# TinyShuffle_v_0b.net
KiCad netlist of a schematic drawn in Altium Designer
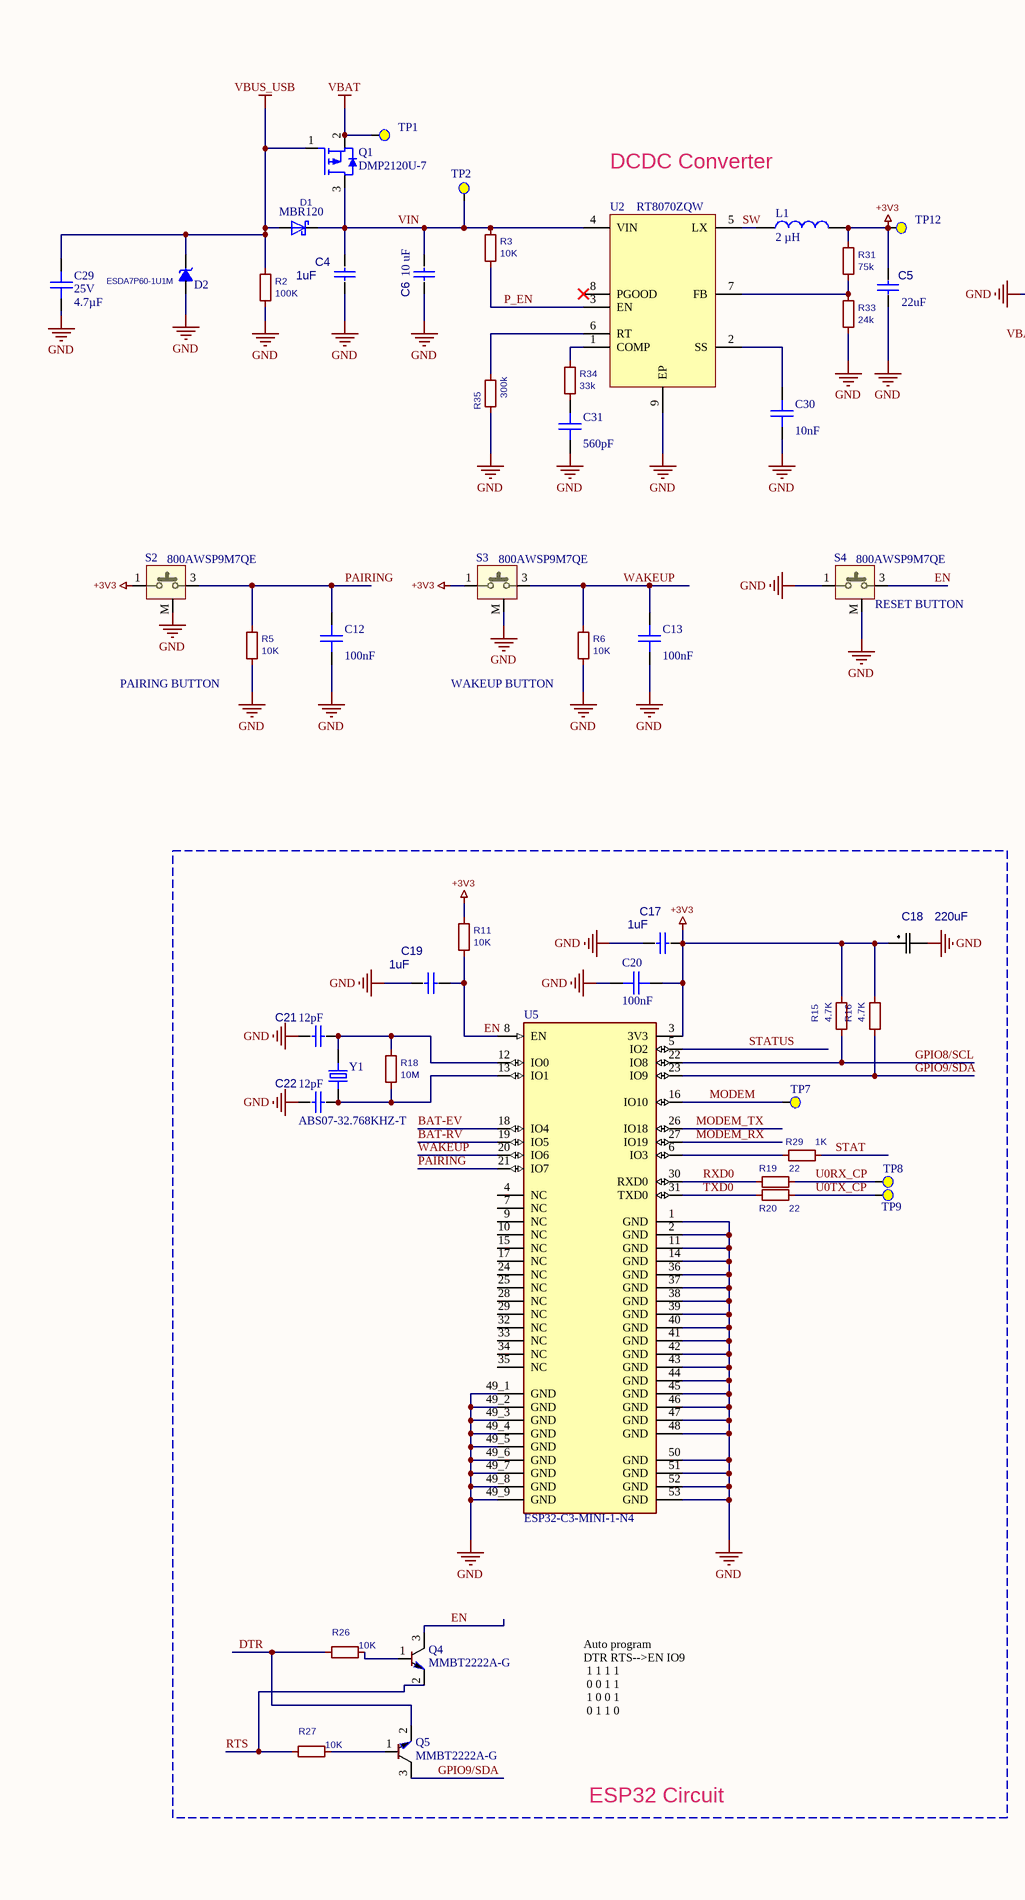
[diagram p0: TinyShuffle v.0b.SchDoc, left]
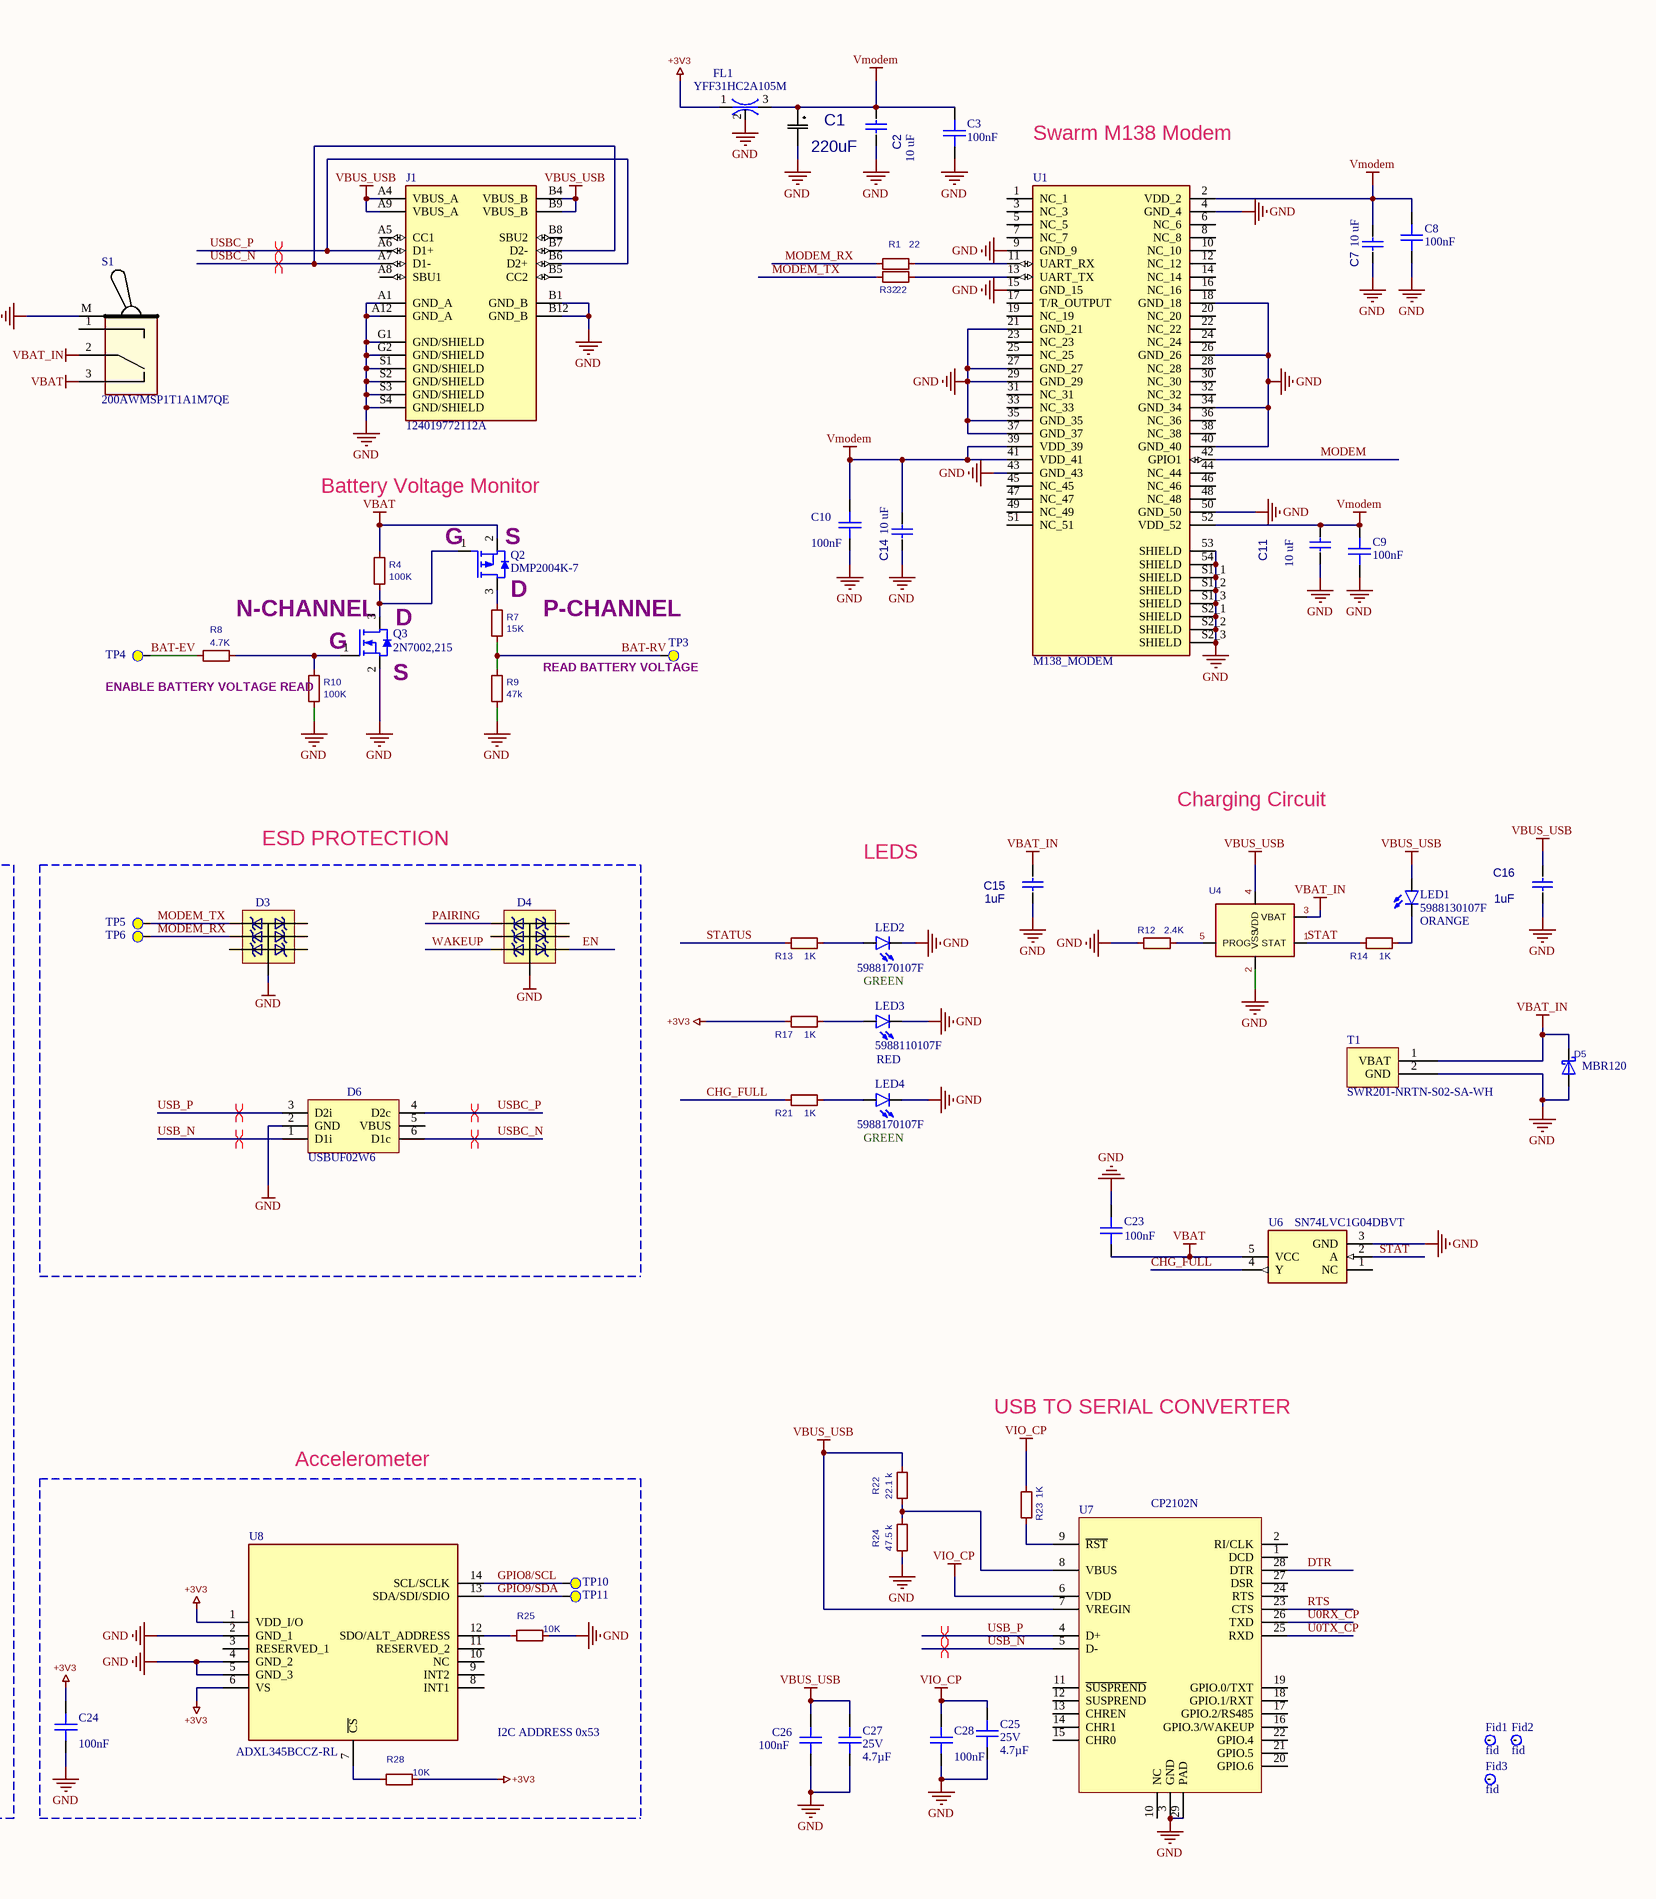
[diagram p1: TinyShuffle v.0b.SchDoc, right]

(export (version "E")
  (design (tool "Eeschema 10.0.6"))
  (components
    (comp (ref "C1")
      (value "220uF")
      (footprint "CHEMI-H70")
      (description "CAP ALUM POLY 220UF 20% 6.3V SMD")
      (fields
        (field (name "MANUFACTURER") "Nippon Chemi-Con")
        (field (name "MANUFACTURERPARTNUMBER") "APXA6R3ARA221MH70G")
        (field (name "COPYRIGHT") "Copyright (C) 2022 Ultra Librarian. All rights reserved.")
      )
      (libsource (lib "TinyShuffle v.0") (part "APXA6R3ARA221MH7"))
    )
    (comp (ref "C2")
      (value "10 uF")
      (footprint "0603 Capacitor")
      (description "25V 10UF X5R ±20% 0603 MLCC")
      (fields
        (field (name "MANUFACTURER") "Samsung Electro-Mechanics")
        (field (name "MANUFACTURERPARTNUMBER") "CL10A106MA8NRNC")
      )
      (libsource (lib "*") (part "CAPC1608N-0.1UF"))
    )
    (comp (ref "C3")
      (value "CL10B104KB8NNWC")
      (footprint "CAPC160X80X90L35L")
      (description "CAP CER 0.1UF 50V X7R 0603")
      (fields
        (field (name "CAPACITANCE") "100nF")
        (field (name "TOLERANCE") "10%")
        (field (name "MANUFACTURER") "Samsung Electro-Mechanics")
      )
      (libsource (lib "VDroid Server") (part "CAP general symbol S00567"))
    )
    (comp (ref "C4")
      (value "1uF")
      (footprint "0603 Capacitor")
      (description "CAP CER 1UF 25V X7R 0603")
      (fields
        (field (name "MANUFACTURER") "YAGEO")
        (field (name "MANUFACTURERPARTNUMBER") "CC0603KRX7R8BB105")
      )
      (libsource (lib "*") (part "CAPC1608N-0.1UF"))
    )
    (comp (ref "C5")
      (value "22uF")
      (footprint "CAPC2012X135N")
      (description "CAP CER 22UF 16V X5R 0805")
      (fields
        (field (name "MANUFACTURER") "Samsung Electro-Mechanics")
        (field (name "MANUFACTURERPARTNUMBER") "CL21A226MOQNNNE")
      )
      (libsource (lib "TinyShuffle v.0") (part "CL21A226MOQNNNE"))
    )
    (comp (ref "C6")
      (value "10 uF")
      (footprint "0603 Capacitor")
      (description "25V 10UF X5R ±20% 0603 MLCC")
      (fields
        (field (name "MANUFACTURER") "Samsung Electro-Mechanics")
        (field (name "MANUFACTURERPARTNUMBER") "CL10A106MA8NRNC")
      )
      (libsource (lib "*") (part "CAPC1608N-0.1UF"))
    )
    (comp (ref "C7")
      (value "10 uF")
      (footprint "0603 Capacitor")
      (description "25V 10UF X5R ±20% 0603 MLCC")
      (fields
        (field (name "MANUFACTURER") "Samsung Electro-Mechanics")
        (field (name "MANUFACTURERPARTNUMBER") "CL10A106MA8NRNC")
      )
      (libsource (lib "*") (part "CAPC1608N-0.1UF"))
    )
    (comp (ref "C8")
      (value "CL10B104KB8NNWC")
      (footprint "CAPC160X80X90L35L")
      (description "CAP CER 0.1UF 50V X7R 0603")
      (fields
        (field (name "CAPACITANCE") "100nF")
        (field (name "TOLERANCE") "10%")
        (field (name "MANUFACTURER") "Samsung Electro-Mechanics")
      )
      (libsource (lib "VDroid Server") (part "CAP general symbol S00567"))
    )
    (comp (ref "C9")
      (value "CL10B104KB8NNWC")
      (footprint "CAPC160X80X90L35L")
      (description "CAP CER 0.1UF 50V X7R 0603")
      (fields
        (field (name "CAPACITANCE") "100nF")
        (field (name "TOLERANCE") "10%")
        (field (name "MANUFACTURER") "Samsung Electro-Mechanics")
      )
      (libsource (lib "VDroid Server") (part "CAP general symbol S00567"))
    )
    (comp (ref "C10")
      (value "CL10B104KB8NNWC")
      (footprint "CAPC160X80X90L35L")
      (description "CAP CER 0.1UF 50V X7R 0603")
      (fields
        (field (name "CAPACITANCE") "100nF")
        (field (name "TOLERANCE") "10%")
        (field (name "MANUFACTURER") "Samsung Electro-Mechanics")
      )
      (libsource (lib "VDroid Server") (part "CAP general symbol S00567"))
    )
    (comp (ref "C11")
      (value "10 uF")
      (footprint "0603 Capacitor")
      (description "25V 10UF X5R ±20% 0603 MLCC")
      (fields
        (field (name "MANUFACTURER") "Samsung Electro-Mechanics")
        (field (name "MANUFACTURERPARTNUMBER") "CL10A106MA8NRNC")
      )
      (libsource (lib "*") (part "CAPC1608N-0.1UF"))
    )
    (comp (ref "C12")
      (value "CL10B104KB8NNWC")
      (footprint "CAPC160X80X90L35L")
      (description "CAP CER 0.1UF 50V X7R 0603")
      (fields
        (field (name "CAPACITANCE") "100nF")
        (field (name "TOLERANCE") "10%")
        (field (name "MANUFACTURER") "Samsung Electro-Mechanics")
      )
      (libsource (lib "VDroid Server") (part "CAP general symbol S00567"))
    )
    (comp (ref "C13")
      (value "CL10B104KB8NNWC")
      (footprint "CAPC160X80X90L35L")
      (description "CAP CER 0.1UF 50V X7R 0603")
      (fields
        (field (name "CAPACITANCE") "100nF")
        (field (name "TOLERANCE") "10%")
        (field (name "MANUFACTURER") "Samsung Electro-Mechanics")
      )
      (libsource (lib "VDroid Server") (part "CAP general symbol S00567"))
    )
    (comp (ref "C14")
      (value "10 uF")
      (footprint "0603 Capacitor")
      (description "25V 10UF X5R ±20% 0603 MLCC")
      (fields
        (field (name "MANUFACTURER") "Samsung Electro-Mechanics")
        (field (name "MANUFACTURERPARTNUMBER") "CL10A106MA8NRNC")
      )
      (libsource (lib "*") (part "CAPC1608N-0.1UF"))
    )
    (comp (ref "C15")
      (value "1uF")
      (footprint "0603 Capacitor")
      (description "CAP CER 1UF 25V X7R 0603")
      (fields
        (field (name "MANUFACTURER") "YAGEO")
        (field (name "MANUFACTURERPARTNUMBER") "CC0603KRX7R8BB105")
      )
      (libsource (lib "*") (part "CAPC1608N-0.1UF"))
    )
    (comp (ref "C16")
      (value "1uF")
      (footprint "0603 Capacitor")
      (description "CAP CER 1UF 25V X7R 0603")
      (fields
        (field (name "MANUFACTURER") "YAGEO")
        (field (name "MANUFACTURERPARTNUMBER") "CC0603KRX7R8BB105")
      )
      (libsource (lib "*") (part "CAPC1608N-0.1UF"))
    )
    (comp (ref "C17")
      (value "1uF")
      (footprint "0603 Capacitor")
      (description "CAP CER 1UF 25V X7R 0603")
      (fields
        (field (name "MANUFACTURER") "YAGEO")
        (field (name "MANUFACTURERPARTNUMBER") "CC0603KRX7R8BB105")
      )
      (libsource (lib "*") (part "CAPC1608N-0.1UF"))
    )
    (comp (ref "C18")
      (value "220uF")
      (footprint "CHEMI-H70")
      (description "CAP ALUM POLY 220UF 20% 6.3V SMD")
      (fields
        (field (name "MANUFACTURER") "Nippon Chemi-Con")
        (field (name "MANUFACTURERPARTNUMBER") "APXA6R3ARA221MH70G")
        (field (name "COPYRIGHT") "Copyright (C) 2022 Ultra Librarian. All rights reserved.")
      )
      (libsource (lib "TinyShuffle v.0") (part "APXA6R3ARA221MH7"))
    )
    (comp (ref "C19")
      (value "1uF")
      (footprint "0603 Capacitor")
      (description "CAP CER 1UF 25V X7R 0603")
      (fields
        (field (name "MANUFACTURER") "YAGEO")
        (field (name "MANUFACTURERPARTNUMBER") "CC0603KRX7R8BB105")
      )
      (libsource (lib "*") (part "CAPC1608N-0.1UF"))
    )
    (comp (ref "C20")
      (value "CL10B104KB8NNWC")
      (footprint "CAPC160X80X90L35L")
      (description "CAP CER 0.1UF 50V X7R 0603")
      (fields
        (field (name "CAPACITANCE") "100nF")
        (field (name "TOLERANCE") "10%")
        (field (name "MANUFACTURER") "Samsung Electro-Mechanics")
      )
      (libsource (lib "VDroid Server") (part "CAP general symbol S00567"))
    )
    (comp (ref "C21")
      (value "12pF")
      (footprint "0603 Capacitor")
      (description "CAP CER 12PF NP0 0603")
      (fields
        (field (name "MANUFACTURER") "Murata Electronics")
        (field (name "MANUFACTURERPARTNUMBER") "GRM1885C2A120JA01D")
      )
      (libsource (lib "*") (part "CAPC1608N-0.1UF"))
    )
    (comp (ref "C22")
      (value "12pF")
      (footprint "0603 Capacitor")
      (description "CAP CER 12PF NP0 0603")
      (fields
        (field (name "MANUFACTURER") "Murata Electronics")
        (field (name "MANUFACTURERPARTNUMBER") "GRM1885C2A120JA01D")
      )
      (libsource (lib "*") (part "CAPC1608N-0.1UF"))
    )
    (comp (ref "C23")
      (value "CL10B104KB8NNWC")
      (footprint "CAPC160X80X90L35L")
      (description "CAP CER 0.1UF 50V X7R 0603")
      (fields
        (field (name "CAPACITANCE") "100nF")
        (field (name "TOLERANCE") "10%")
        (field (name "MANUFACTURER") "Samsung Electro-Mechanics")
      )
      (libsource (lib "VDroid Server") (part "CAP general symbol S00567"))
    )
    (comp (ref "C24")
      (value "CL10B104KB8NNWC")
      (footprint "CAPC160X80X90L35L")
      (description "CAP CER 0.1UF 50V X7R 0603")
      (fields
        (field (name "CAPACITANCE") "100nF")
        (field (name "TOLERANCE") "10%")
        (field (name "MANUFACTURER") "Samsung Electro-Mechanics")
      )
      (libsource (lib "VDroid Server") (part "CAP general symbol S00567"))
    )
    (comp (ref "C25")
      (value "GRM188R61E475KE11D")
      (footprint "CAPC160X80X90L35L")
      (description "CAP CER 4.7UF 25V X5R 0603")
      (fields
        (field (name "VOLTAGE RATING") "25V")
        (field (name "TOLERANCE") "10%")
        (field (name "CAPACITANCE") "4.7µF")
        (field (name "MANUFACTURER") "Murata Electronics")
      )
      (libsource (lib "VDroid Server") (part "CAP general symbol S00567"))
    )
    (comp (ref "C26")
      (value "CL10B104KB8NNWC")
      (footprint "CAPC160X80X90L35L")
      (description "CAP CER 0.1UF 50V X7R 0603")
      (fields
        (field (name "CAPACITANCE") "100nF")
        (field (name "TOLERANCE") "10%")
        (field (name "MANUFACTURER") "Samsung Electro-Mechanics")
      )
      (libsource (lib "VDroid Server") (part "CAP general symbol S00567"))
    )
    (comp (ref "C27")
      (value "GRM188R61E475KE11D")
      (footprint "CAPC160X80X90L35L")
      (description "CAP CER 4.7UF 25V X5R 0603")
      (fields
        (field (name "VOLTAGE RATING") "25V")
        (field (name "TOLERANCE") "10%")
        (field (name "CAPACITANCE") "4.7µF")
        (field (name "MANUFACTURER") "Murata Electronics")
      )
      (libsource (lib "VDroid Server") (part "CAP general symbol S00567"))
    )
    (comp (ref "C28")
      (value "CL10B104KB8NNWC")
      (footprint "CAPC160X80X90L35L")
      (description "CAP CER 0.1UF 50V X7R 0603")
      (fields
        (field (name "CAPACITANCE") "100nF")
        (field (name "TOLERANCE") "10%")
        (field (name "MANUFACTURER") "Samsung Electro-Mechanics")
      )
      (libsource (lib "VDroid Server") (part "CAP general symbol S00567"))
    )
    (comp (ref "C29")
      (value "GRM188R61E475KE11D")
      (footprint "CAPC160X80X90L35L")
      (description "CAP CER 4.7UF 25V X5R 0603")
      (fields
        (field (name "VOLTAGE RATING") "25V")
        (field (name "TOLERANCE") "10%")
        (field (name "CAPACITANCE") "4.7µF")
        (field (name "MANUFACTURER") "Murata Electronics")
      )
      (libsource (lib "VDroid Server") (part "CAP general symbol S00567"))
    )
    (comp (ref "C30")
      (value "CL10B103KB8NNNC")
      (footprint "CAPC160X80X90L35L")
      (description "CAP CER 10000PF 50V X7R 0603")
      (fields
        (field (name "CAPACITANCE") "10nF")
        (field (name "TOLERANCE") "10%")
        (field (name "MANUFACTURER") "Samsung Electro-Mechanics")
      )
      (libsource (lib "VDroid Server") (part "CAP general symbol S00567"))
    )
    (comp (ref "C31")
      (value "CL10C561JB8NFNC")
      (footprint "CAPC160X80X90L35L")
      (description "CAP CER 560PF 50V C0G/NP0 0603")
      (fields
        (field (name "CAPACITANCE") "560pF")
        (field (name "TOLERANCE") "10%")
        (field (name "MANUFACTURER") "Samsung Electro-Mechanics")
      )
      (libsource (lib "VDroid Server") (part "CAP general symbol S00567"))
    )
    (comp (ref "D1")
      (value "MBR120")
      (footprint "SODFL3616X98N")
      (description "20V 600mV@1A 1A SOD-123 Schottky Barrier Diodes (SBD) ROHS")
      (fields (field (name "MANUFACTURERPARTNUMBER") "LMBR120FT1G") (field (name "GENERIC PART") "no"))
      (libsource (lib "TinyShuffle v.0b") (part "MBR0520"))
    )
    (comp (ref "D2")
      (value "ESDA7P60-1U1M")
      (footprint "ST_1610")
      (description "TVS DIODE 5V 11.6V 1610")
      (fields (field (name "MANUFACTURER") "STMicroelectronics"))
      (libsource (lib "Diodes") (part "ESDA7P60-1U1M"))
    )
    (comp (ref "D3")
      (value "UCLAMP3306P.TCT")
      (footprint "SLP1616P6")
      (description "TVS DIODE 3.3V 8V SLP1616P6")
      (fields (field (name "MANUFACTURER") "Semtech"))
      (libsource (lib "Diodes") (part "UCLAMP3306P.TCT"))
    )
    (comp (ref "D4")
      (value "UCLAMP3306P.TCT")
      (footprint "SLP1616P6")
      (description "TVS DIODE 3.3V 8V SLP1616P6")
      (fields (field (name "MANUFACTURER") "Semtech"))
      (libsource (lib "Diodes") (part "UCLAMP3306P.TCT"))
    )
    (comp (ref "D5")
      (value "MBR120")
      (footprint "SODFL3616X98N")
      (description "20V 600mV@1A 1A SOD-123 Schottky Barrier Diodes (SBD) ROHS")
      (fields (field (name "MANUFACTURERPARTNUMBER") "LMBR120FT1G") (field (name "GENERIC PART") "no"))
      (libsource (lib "TinyShuffle v.0b") (part "MBR0520"))
    )
    (comp (ref "D6")
      (value "USBUF02W6")
      (footprint "SOT323-6L")
      (description "FILTER RC(PI) 22 OHM/47PF SMD")
      (fields (field (name "MANUFACTURER") "STMicroelectronics"))
      (libsource (lib "Diodes") (part "NUF2221W1T2G"))
    )
    (comp (ref "Fid1") (value "fid") (footprint "Fiducial mark 1") (libsource (lib "SensiEdge") (part "fid")))
    (comp (ref "Fid2") (value "fid") (footprint "Fiducial mark 1") (libsource (lib "SensiEdge") (part "fid")))
    (comp (ref "Fid3") (value "fid") (footprint "Fiducial mark 1") (libsource (lib "SensiEdge") (part "fid")))
    (comp (ref "FL1")
      (value "YFF31HC2A105M")
      (footprint "FIL_YFF31HC2A105M")
      (description "1ÂµF Feed Through Capacitor 100V 6A 5mOhm 1206 (3216 Metric), 4 PC Pad")
      (fields (field (name "MANUFACTURER") "TDK") (field (name "DIGI-KEY_PART_NUMBER") "445-16151-1-ND"))
      (libsource (lib "TinyShuffle v.0") (part "YFF31HC2A105M"))
    )
    (comp (ref "J1")
      (value "124019772112A")
      (footprint "TinyShuffle v.0:AMPHENOL_124019772112A")
      (description "USB2.0, TOP MOUNT, R/A, 16 PIN, DUAL")
      (fields (field (name "MANUFACTURER") "Amphenol Commercial Products"))
      (libsource (lib "TinyShuffle v.0") (part "124019772112A"))
    )
    (comp (ref "L1")
      (value "2 µH")
      (footprint "INDC8080X42L")
      (description "FIXED IND 2UH 6.3A 11.7 MOHM SMD")
      (fields
        (field (name "MANUFACTURERPARTNUMBER") "NR8040T2R0N")
        (field (name "MANUFACTURER") "Taiyo Yuden")
      )
      (libsource (lib "TinyShuffle v.0") (part "NR8040T2R0N"))
    )
    (comp (ref "LED1")
      (value "5988130107F")
      (footprint "TinyShuffle v.0:LEDC2012X70N")
      (description "Orange 605nm LED Indication - Discrete 2V 0805 (2012 Metric)")
      (fields
        (field (name "MANUFACTURERPARTNUMBER") "598-8110-107F")
        (field (name "MANUFACTURER") "Dialight")
        (field (name "ALTIUM_VALUE") "ORANGE")
      )
      (libsource (lib "TinyShuffle v.0") (part "598_SERIES_LED"))
    )
    (comp (ref "LED2")
      (value "5988170107F")
      (footprint "LEDC2012X70N")
      (description "Green 566nm LED Indication - Discrete 2V 0805 (2012 Metric)")
      (fields
        (field (name "MANUFACTURERPARTNUMBER") "598-8110-107F")
        (field (name "MANUFACTURER") "Dialight")
        (field (name "ALTIUM_VALUE") "GREEN")
      )
      (libsource (lib "TinyShuffle v.0") (part "598_SERIES_LED"))
    )
    (comp (ref "LED3")
      (value "5988110107F")
      (footprint "TinyShuffle v.0:LEDC2012X70N")
      (description "Red 635nm LED Indication - Discrete 2.2V 0805 _2012 Metric_")
      (fields
        (field (name "MANUFACTURERPARTNUMBER") "598-8110-107F")
        (field (name "MANUFACTURER") "Dialight")
        (field (name "ALTIUM_VALUE") "RED")
      )
      (libsource (lib "TinyShuffle v.0") (part "598_SERIES_LED"))
    )
    (comp (ref "LED4")
      (value "5988170107F")
      (footprint "TinyShuffle v.0:LEDC2012X70N")
      (description "Green 566nm LED Indication - Discrete 2V 0805 (2012 Metric)")
      (fields
        (field (name "MANUFACTURERPARTNUMBER") "598-8110-107F")
        (field (name "MANUFACTURER") "Dialight")
        (field (name "ALTIUM_VALUE") "GREEN")
      )
      (libsource (lib "TinyShuffle v.0") (part "598_SERIES_LED"))
    )
    (comp (ref "Q1")
      (value "DMP2120U-7")
      (footprint "SOT23-3P95_237X112L50X40L")
      (description "MOSFET P-CH 20V 3.8A SOT23")
      (fields (field (name "MANUFACTURER") "Diodes Incorporated"))
      (libsource (lib "VDroid Server") (part "P-type channel MOSFET S00673 (1-G 2-S 3-D)"))
    )
    (comp (ref "Q2")
      (value "DMP2004K-7")
      (footprint "SOT23-3P95_237X112L50X40L")
      (description "MOSFET P-CH 20V 600MA SOT23-3")
      (fields (field (name "MANUFACTURER") "Diodes Incorporated"))
      (libsource (lib "VDroid Server") (part "P-type channel MOSFET S00673 (1-G 2-S 3-D)"))
    )
    (comp (ref "Q3")
      (value "2N7002,215")
      (footprint "SOT23-3P95_237X112L50X40L")
      (description "Power MOSFET, N Channel, 60 V, 300 mA, 2.8 ohm, SOT-23, Surface Mount")
      (fields (field (name "MANUFACTURER") "Nexperia USA Inc."))
      (libsource (lib "VDroid Server") (part "N-type channel MOSFET S00674 (1-G 2-S 3-D)"))
    )
    (comp (ref "Q4")
      (value "MMBT2222A-G")
      (footprint "SOT96P237X111-3N")
      (description "Integrated Circuit")
      (fields
        (field (name "MANUFACTURER") "Comchip Technology")
        (field (name "MOUSER PART NUMBER") "863-MMBT2222ALT1G")
      )
      (libsource (lib "TinyShuffle v.0") (part "MMBT2222ALT1G"))
    )
    (comp (ref "Q5")
      (value "MMBT2222A-G")
      (footprint "SOT96P237X111-3N")
      (description "Integrated Circuit")
      (fields
        (field (name "MANUFACTURER") "Comchip Technology")
        (field (name "MOUSER PART NUMBER") "863-MMBT2222ALT1G")
      )
      (libsource (lib "") (part "MMBT2222ALT1G_1"))
    )
    (comp (ref "R1")
      (value "22")
      (footprint "RES0603")
      (description "RES 22OHM 1/10W 1% 0603 SMD")
      (fields (field (name "MANUFACTURERPARTNUMBER") "RC0603FR-0722RL") (field (name "GENERIC PART") "no"))
      (libsource (lib "Vishay_Res_SMD") (part "1K_0603"))
    )
    (comp (ref "R2")
      (value "100K")
      (footprint "RES0603")
      (description "Res General Purpose Thick Film 0603 100k Ohm 1% 1/10W ±100ppm/°C Molded")
      (fields (field (name "MANUFACTURERPARTNUMBER") "CRCW0603100KFKEAHP") (field (name "GENERIC PART") "no"))
      (libsource (lib "Vishay_Res_SMD") (part "100K_0603"))
    )
    (comp (ref "R3")
      (value "10K")
      (footprint "RES0603")
      (description "RES 10.0K OHM 1/10W 1% 0603 SMD Ro HS")
      (fields (field (name "MANUFACTURERPARTNUMBER") "RGA1608P-103-B-T1") (field (name "GENERIC PART") "no"))
      (libsource (lib "Vishay_Res_SMD") (part "100K_0603"))
    )
    (comp (ref "R4")
      (value "100K")
      (footprint "RES0603")
      (description "Res General Purpose Thick Film 0603 100k Ohm 1% 1/10W ±100ppm/°C Molded")
      (fields (field (name "MANUFACTURERPARTNUMBER") "CRCW0603100KFKEAHP") (field (name "GENERIC PART") "no"))
      (libsource (lib "Vishay_Res_SMD") (part "100K_0603"))
    )
    (comp (ref "R5")
      (value "10K")
      (footprint "RES0603")
      (description "RES 10.0K OHM 1/10W 1% 0603 SMD Ro HS")
      (fields (field (name "MANUFACTURERPARTNUMBER") "RGA1608P-103-B-T1") (field (name "GENERIC PART") "no"))
      (libsource (lib "Vishay_Res_SMD") (part "100K_0603"))
    )
    (comp (ref "R6")
      (value "10K")
      (footprint "RES0603")
      (description "RES 10.0K OHM 1/10W 1% 0603 SMD Ro HS")
      (fields (field (name "MANUFACTURERPARTNUMBER") "RGA1608P-103-B-T1") (field (name "GENERIC PART") "no"))
      (libsource (lib "Vishay_Res_SMD") (part "100K_0603"))
    )
    (comp (ref "R7")
      (value "15K")
      (footprint "RES0603")
      (description "RES 15K OHM 1% 1/10W 0603")
      (fields (field (name "MANUFACTURERPARTNUMBER") "CRCW060315K0FKEAC") (field (name "GENERIC PART") "no"))
      (libsource (lib "Vishay_Res_SMD") (part "330K_0603"))
    )
    (comp (ref "R8")
      (value "4.7K")
      (footprint "RES0603")
      (description "Thin Film Resistors - SMD 1/10W 4.7K ohm 1% 50ppm")
      (fields (field (name "MANUFACTURERPARTNUMBER") "RT0603FRE074K7L") (field (name "MANUFACTURER") "YAGEO"))
      (libsource (lib "") (part "100K_0603_2"))
    )
    (comp (ref "R9")
      (value "47k")
      (footprint "RES0603")
      (description "RES SMD 47K OHM 1% 1/10W 0603")
      (fields (field (name "MANUFACTURERPARTNUMBER") "CRCW060347K0FKTA") (field (name "GENERIC PART") "no"))
      (libsource (lib "Vishay_Res_SMD") (part "100K_0603"))
    )
    (comp (ref "R10")
      (value "100K")
      (footprint "RES0603")
      (description "Res General Purpose Thick Film 0603 100k Ohm 1% 1/10W ±100ppm/°C Molded")
      (fields (field (name "MANUFACTURERPARTNUMBER") "CRCW0603100KFKEAHP") (field (name "GENERIC PART") "no"))
      (libsource (lib "Vishay_Res_SMD") (part "100K_0603"))
    )
    (comp (ref "R11")
      (value "10K")
      (footprint "RES0603")
      (description "RES 10.0K OHM 1/10W 1% 0603 SMD Ro HS")
      (fields (field (name "MANUFACTURERPARTNUMBER") "RGA1608P-103-B-T1") (field (name "GENERIC PART") "no"))
      (libsource (lib "Vishay_Res_SMD") (part "100K_0603"))
    )
    (comp (ref "R12")
      (value "2.4K")
      (footprint "RES0603")
      (description "2.4 kOhms ±1% 0.1W, 1/10W Chip Resistor 0603 (1608 Metric) Thick Film")
      (fields (field (name "MANUFACTURERPARTNUMBER") "CRCW06032K40FKEAC") (field (name "GENERIC PART") "no"))
      (libsource (lib "Vishay_Res_SMD") (part "10K_0603"))
    )
    (comp (ref "R13")
      (value "1K")
      (footprint "RES0603")
      (description "RES 1.00K OHM 1/10W 1% 0603 SMD")
      (fields (field (name "MANUFACTURERPARTNUMBER") "CRCW06031K00FKEAHP") (field (name "GENERIC PART") "no"))
      (libsource (lib "Vishay_Res_SMD") (part "1K_0603"))
    )
    (comp (ref "R14")
      (value "1K")
      (footprint "RES0603")
      (description "RES 1.00K OHM 1/10W 1% 0603 SMD")
      (fields (field (name "MANUFACTURERPARTNUMBER") "CRCW06031K00FKEAHP") (field (name "GENERIC PART") "no"))
      (libsource (lib "Vishay_Res_SMD") (part "1K_0603"))
    )
    (comp (ref "R15")
      (value "4.7K")
      (footprint "RES0603")
      (description "Thin Film Resistors - SMD 1/10W 4.7K ohm 1% 50ppm")
      (fields (field (name "MANUFACTURERPARTNUMBER") "RT0603FRE074K7L") (field (name "MANUFACTURER") "YAGEO"))
      (libsource (lib "") (part "100K_0603_1"))
    )
    (comp (ref "R16")
      (value "4.7K")
      (footprint "RES0603")
      (description "Thin Film Resistors - SMD 1/10W 4.7K ohm 1% 50ppm")
      (fields (field (name "MANUFACTURERPARTNUMBER") "RT0603FRE074K7L") (field (name "MANUFACTURER") "YAGEO"))
      (libsource (lib "") (part "100K_0603_1"))
    )
    (comp (ref "R17")
      (value "1K")
      (footprint "RES0603")
      (description "RES 1.00K OHM 1/10W 1% 0603 SMD")
      (fields (field (name "MANUFACTURERPARTNUMBER") "CRCW06031K00FKEAHP") (field (name "GENERIC PART") "no"))
      (libsource (lib "Vishay_Res_SMD") (part "1K_0603"))
    )
    (comp (ref "R18")
      (value "10M")
      (footprint "RES0603")
      (description "Res Thick Film 0603 10M Ohm 1% 1/10W ±200ppm/°C Molded SMD SMD Paper T/R")
      (fields (field (name "GENERIC PART") "YES") (field (name "MANUFACTURERPARTNUMBER") "CRCW060310M0JNEA"))
      (libsource (lib "Vishay_Res_SMD") (part "100K_0603"))
    )
    (comp (ref "R19")
      (value "22")
      (footprint "RES0603")
      (description "RES 22OHM 1/10W 1% 0603 SMD")
      (fields (field (name "MANUFACTURERPARTNUMBER") "RC0603FR-0722RL") (field (name "GENERIC PART") "no"))
      (libsource (lib "Vishay_Res_SMD") (part "1K_0603"))
    )
    (comp (ref "R20")
      (value "22")
      (footprint "RES0603")
      (description "RES 22OHM 1/10W 1% 0603 SMD")
      (fields (field (name "MANUFACTURERPARTNUMBER") "RC0603FR-0722RL") (field (name "GENERIC PART") "no"))
      (libsource (lib "Vishay_Res_SMD") (part "1K_0603"))
    )
    (comp (ref "R21")
      (value "1K")
      (footprint "RES0603")
      (description "RES 1.00K OHM 1/10W 1% 0603 SMD")
      (fields (field (name "MANUFACTURERPARTNUMBER") "CRCW06031K00FKEAHP") (field (name "GENERIC PART") "no"))
      (libsource (lib "Vishay_Res_SMD") (part "1K_0603"))
    )
    (comp (ref "R22")
      (value "22.1 k")
      (footprint "RES0603")
      (description "RES SMD 22.1K OHM 1% 1/10W 0603")
      (fields
        (field (name "MANUFACTURERPARTNUMBER") "CRCW060322K1FKEA")
        (field (name "MANUFACTURER") "Vishay")
      )
      (libsource (lib "") (part "1K_0603_1"))
    )
    (comp (ref "R23")
      (value "1K")
      (footprint "RES0603")
      (description "RES 1.00K OHM 1/10W 1% 0603 SMD")
      (fields (field (name "MANUFACTURERPARTNUMBER") "CRCW06031K00FKEAHP") (field (name "GENERIC PART") "no"))
      (libsource (lib "") (part "1K_0603_1"))
    )
    (comp (ref "R24")
      (value "47.5 k")
      (footprint "RES0603")
      (description "RES 47.5K OHM 1% 1/10W 0603")
      (fields
        (field (name "MANUFACTURERPARTNUMBER") "CRCW060347K5FKEAC")
        (field (name "MANUFACTURER") "Vishay")
      )
      (libsource (lib "") (part "1K_0603_1"))
    )
    (comp (ref "R25")
      (value "10K")
      (footprint "RES0603")
      (description "RES 10.0K OHM 1/10W 1% 0603 SMD Ro HS")
      (fields (field (name "MANUFACTURERPARTNUMBER") "RGA1608P-103-B-T1") (field (name "GENERIC PART") "no"))
      (libsource (lib "") (part "100K_0603_2"))
    )
    (comp (ref "R26")
      (value "10K")
      (footprint "RES0603")
      (description "RES 10.0K OHM 1/10W 1% 0603 SMD Ro HS")
      (fields (field (name "MANUFACTURERPARTNUMBER") "RGA1608P-103-B-T1") (field (name "GENERIC PART") "no"))
      (libsource (lib "") (part "100K_0603_2"))
    )
    (comp (ref "R27")
      (value "10K")
      (footprint "RES0603")
      (description "RES 10.0K OHM 1/10W 1% 0603 SMD Ro HS")
      (fields (field (name "MANUFACTURERPARTNUMBER") "RGA1608P-103-B-T1") (field (name "GENERIC PART") "no"))
      (libsource (lib "") (part "100K_0603_2"))
    )
    (comp (ref "R28")
      (value "10K")
      (footprint "RES0603")
      (description "RES 10.0K OHM 1/10W 1% 0603 SMD Ro HS")
      (fields (field (name "MANUFACTURERPARTNUMBER") "RGA1608P-103-B-T1") (field (name "GENERIC PART") "no"))
      (libsource (lib "") (part "100K_0603_2"))
    )
    (comp (ref "R29")
      (value "1K")
      (footprint "RES0603")
      (description "RES 1.00K OHM 1/10W 1% 0603 SMD")
      (fields (field (name "MANUFACTURERPARTNUMBER") "CRCW06031K00FKEAHP") (field (name "GENERIC PART") "no"))
      (libsource (lib "Vishay_Res_SMD") (part "1K_0603"))
    )
    (comp (ref "R31")
      (value "75k")
      (footprint "RES0603")
      (description "RES 75K OHM 1% 1/10W 0603")
      (fields (field (name "MANUFACTURERPARTNUMBER") "CRCW060375K0FKEAC") (field (name "GENERIC PART") "no"))
      (libsource (lib "Vishay_Res_SMD") (part "100K_0603"))
    )
    (comp (ref "R32")
      (value "22")
      (footprint "RES0603")
      (description "RES 22OHM 1/10W 1% 0603 SMD")
      (fields (field (name "MANUFACTURERPARTNUMBER") "RC0603FR-0722RL") (field (name "GENERIC PART") "no"))
      (libsource (lib "Vishay_Res_SMD") (part "1K_0603"))
    )
    (comp (ref "R33")
      (value "24k")
      (footprint "RES0603")
      (description "RES 24K OHM 1% 1/10W 0603")
      (fields (field (name "MANUFACTURERPARTNUMBER") "CRCW060324K0FKEAC") (field (name "GENERIC PART") "no"))
      (libsource (lib "Vishay_Res_SMD") (part "100K_0603"))
    )
    (comp (ref "R34")
      (value "33k")
      (footprint "RES0603")
      (description "RES SMD 33K OHM 1% 1/10W 0603")
      (fields (field (name "MANUFACTURERPARTNUMBER") "RT0603DRE0733KL") (field (name "GENERIC PART") "no"))
      (libsource (lib "Vishay_Res_SMD") (part "100K_0603"))
    )
    (comp (ref "R35")
      (value "300k")
      (footprint "RES0603")
      (description "RES 300K OHM 5% 1/10W 0603")
      (fields (field (name "MANUFACTURERPARTNUMBER") "RC0603JR-07300KL") (field (name "GENERIC PART") "no"))
      (libsource (lib "") (part "1K_0603_1"))
    )
    (comp (ref "S1")
      (value "200AWMSP1T1A1M7QE")
      (footprint "200AWMSP1T1A1M7QE")
      (description "SWITCH TOGGLE SPDT 3A 120V")
      (fields (field (name "MANUFACTURER") "E-Switch"))
      (libsource (lib "TinyShuffle v.0") (part "200AWMSP1T1A1M7QE"))
    )
    (comp (ref "S2")
      (value "800AWSP9M7QE")
      (footprint "800AWSP9M7QE")
      (description "Pushbutton Switch SPST-NO Standard Through Hole, Right Angle, Vertical")
      (fields (field (name "MANUFACTURER") "E-Switch"))
      (libsource (lib "TinyShuffle v.0") (part "800AWSP9M7QE"))
    )
    (comp (ref "S3")
      (value "800AWSP9M7QE")
      (footprint "800AWSP9M7QE")
      (description "Pushbutton Switch SPST-NO Standard Through Hole, Right Angle, Vertical")
      (fields (field (name "MANUFACTURER") "E-Switch"))
      (libsource (lib "TinyShuffle v.0") (part "800AWSP9M7QE"))
    )
    (comp (ref "S4")
      (value "800AWSP9M7QE")
      (footprint "800AWSP9M7QE")
      (description "Pushbutton Switch SPST-NO Standard Through Hole, Right Angle, Vertical")
      (fields (field (name "MANUFACTURER") "E-Switch"))
      (libsource (lib "TinyShuffle v.0") (part "800AWSP9M7QE"))
    )
    (comp (ref "T1")
      (value "SWR201-NRTN-S02-SA-WH")
      (footprint "JST_B2B-PH-K-S(LF)(SN)")
      (description "Connector Header, PH Series, 2 Position, 2.00mm, Through Hole, Press-Fit, Solder, Natural")
      (fields (field (name "MANUFACTURER") "Sullins Connector Solutions"))
      (libsource (lib "Schlib1") (part "Battery Connector"))
    )
    (comp (ref "TP1")
      (value "TPAD")
      (footprint "PAD_2.0R")
      (description "Test Pad, SMD")
      (libsource (lib "Others") (part "TPAD"))
    )
    (comp (ref "TP2")
      (value "TPAD")
      (footprint "PAD_2.0R")
      (description "Test Pad, SMD")
      (libsource (lib "Others") (part "TPAD"))
    )
    (comp (ref "TP3")
      (value "TPAD")
      (footprint "PAD_2.0R")
      (description "Test Pad, SMD")
      (libsource (lib "Others") (part "TPAD"))
    )
    (comp (ref "TP4")
      (value "TPAD")
      (footprint "PAD_2.0R")
      (description "Test Pad, SMD")
      (libsource (lib "Others") (part "TPAD"))
    )
    (comp (ref "TP5")
      (value "TPAD")
      (footprint "PAD_2.0R")
      (description "Test Pad, SMD")
      (libsource (lib "Others") (part "TPAD"))
    )
    (comp (ref "TP6")
      (value "TPAD")
      (footprint "PAD_2.0R")
      (description "Test Pad, SMD")
      (libsource (lib "Others") (part "TPAD"))
    )
    (comp (ref "TP7")
      (value "TPAD")
      (footprint "PAD_2.0R")
      (description "Test Pad, SMD")
      (libsource (lib "Others") (part "TPAD"))
    )
    (comp (ref "TP8")
      (value "TPAD")
      (footprint "PAD_2.0R")
      (description "Test Pad, SMD")
      (libsource (lib "Others") (part "TPAD"))
    )
    (comp (ref "TP9")
      (value "TPAD")
      (footprint "PAD_2.0R")
      (description "Test Pad, SMD")
      (libsource (lib "Others") (part "TPAD"))
    )
    (comp (ref "TP10")
      (value "TPAD")
      (footprint "PAD_2.0R")
      (description "Test Pad, SMD")
      (libsource (lib "Others") (part "TPAD"))
    )
    (comp (ref "TP11")
      (value "TPAD")
      (footprint "PAD_2.0R")
      (description "Test Pad, SMD")
      (libsource (lib "Others") (part "TPAD"))
    )
    (comp (ref "TP12")
      (value "TPAD")
      (footprint "PAD_2.0R")
      (description "Test Pad, SMD")
      (libsource (lib "Others") (part "TPAD"))
    )
    (comp (ref "U1")
      (value "M138_MODEM")
      (footprint "XCVR_M138_MODEM")
      (description "'SWARM M138 MODEM mPCIe 2.005\" (50.925mm) x 1.18\" (30mm)  Two part connector")
      (fields
        (field (name "MANUFACTURER") "Swarm")
        (field (name "MANUFACTURERPARTNUMBER") "A: MM60-52B1-B1-R850 B: MM60-EZH039-B5-R850")
      )
      (libsource (lib "TinyShuffle v.0") (part "M138_MODEM"))
    )
    (comp (ref "U2")
      (value "RT8070ZQW")
      (footprint "QFN65P300X300X80_HS-9L")
      (description "IC REG BUCK ADJUSTABLE 4A 8WDFN")
      (fields (field (name "MANUFACTURER") "Richtek USA Inc."))
      (libsource (lib "TinyShuffle v.0") (part "RT8070ZQW"))
    )
    (comp (ref "U4")
      (value "MCP73831T-2ACI/OT")
      (footprint "SOT95P270X145-5N")
      (description "IC BATT CNTL LI-ION 1CEL SOT23-5")
      (fields (field (name "GENERIC PART") "no") (field (name "MANUFACTURER") "Microchip Technology"))
      (libsource (lib "TinyShuffle v.0b") (part "MCP73831-2-OT"))
    )
    (comp (ref "U5")
      (value "ESP32-C3-MINI-1-N4")
      (footprint "TinyShuffle v.0:XCVR_ESP32-C3-MINI-1-N4")
      (fields (field (name "MANUFACTURER") "Espressif Systems"))
      (libsource (lib "TinyShuffle v.0") (part "ESP32-C3-MINI-1-N4"))
    )
    (comp (ref "U6")
      (value "SN74LVC1G04DBVT")
      (footprint "SOT95P270X145-5N")
      (description "Inverter IC 1 Channel - SOT-23-5")
      (fields (field (name "MANUFACTURER") "Texas Instruments"))
      (libsource (lib "*") (part "SN74LVC1G04DBVR"))
    )
    (comp (ref "U7")
      (value "CP2102N")
      (footprint "QFN-28_1")
      (description "IC USB TO UART BRIDGE QFN28")
      (fields
        (field (name "MANUFACTURERPARTNUMBER") "CP2102N-A02-GQFN28R")
        (field (name "MANUFACTURER") "Silicon Labs")
      )
      (libsource (lib "TinyShuffle v.0") (part "CP2102N_QFN28"))
    )
    (comp (ref "U8")
      (value "ADXL345BCCZ-RL")
      (footprint "ADXL345BCCZRL")
      (description "3-Axis, ±2 g/±4 g/±8 g/±16 g Digital Accelerometer")
      (fields
        (field (name "MANUFACTURER") "Analog Devices")
        (field (name "MOUSER PART NUMBER") "584-ADXL345BCCZ-R")
      )
      (libsource (lib "*") (part "ADXL345BCCZ-RL"))
    )
    (comp (ref "Y1")
      (value "ABS07-32.768KHZ-T")
      (footprint "TinyShuffle v.0:XTAL_ABS07-32.768KHZ-T")
      (description "32.768kHz Â±20ppm Crystal 12.5pF 70 kOhms 2-SMD, No Lead")
      (fields
        (field (name "MANUFACTURER") "Abracon LLC")
        (field (name "MANUFACTURERPARTNUMBER") "ABS07-32.768KHZ")
      )
      (libsource (lib "TinyShuffle v.0") (part "ABS07-32.768KHZ-T"))
    )
  )
  (nets
    (net (code "1") (name "+3V3") (class "Default")
      (node (ref "C17") (pin "2") (pinfunction "2_2") (pintype "passive"))
      (node (ref "C18") (pin "1") (pinfunction "1_1") (pintype "passive"))
      (node (ref "C20") (pin "1") (pinfunction "1_1") (pintype "passive"))
      (node (ref "C24") (pin "2") (pinfunction "2_2") (pintype "passive"))
      (node (ref "C5") (pin "2") (pinfunction "2_2") (pintype "passive"))
      (node (ref "FL1") (pin "1") (pinfunction "IN/OUT_1") (pintype "passive"))
      (node (ref "L1") (pin "2") (pinfunction "2_2") (pintype "passive"))
      (node (ref "R11") (pin "1") (pinfunction "1_1") (pintype "passive"))
      (node (ref "R15") (pin "2") (pinfunction "2_2") (pintype "passive"))
      (node (ref "R16") (pin "2") (pinfunction "2_2") (pintype "passive"))
      (node (ref "R17") (pin "2") (pinfunction "2_2") (pintype "passive"))
      (node (ref "R28") (pin "2") (pinfunction "2_2") (pintype "passive"))
      (node (ref "R31") (pin "1") (pinfunction "1_1") (pintype "passive"))
      (node (ref "S2") (pin "1") (pinfunction "1_1") (pintype "passive"))
      (node (ref "S3") (pin "1") (pinfunction "1_1") (pintype "passive"))
      (node (ref "TP12") (pin "1") (pinfunction "TPoint_1") (pintype "passive"))
      (node (ref "U5") (pin "3") (pinfunction "3V3_3") (pintype "power_in"))
      (node (ref "U8") (pin "1") (pinfunction "VDD_I/O_1") (pintype "passive"))
      (node (ref "U8") (pin "6") (pinfunction "VS_6") (pintype "passive"))
    )
    (net (code "2") (name "/BAT-EV") (class "Default")
      (node (ref "R8") (pin "1") (pinfunction "1_1") (pintype "passive"))
      (node (ref "TP4") (pin "1") (pinfunction "TPoint_1") (pintype "passive"))
      (node (ref "U5") (pin "18") (pinfunction "IO4_18") (pintype "bidirectional"))
    )
    (net (code "3") (name "/BAT-RV") (class "Default")
      (node (ref "R7") (pin "2") (pinfunction "2_2") (pintype "passive"))
      (node (ref "R9") (pin "1") (pinfunction "1_1") (pintype "passive"))
      (node (ref "TP3") (pin "1") (pinfunction "TPoint_1") (pintype "passive"))
      (node (ref "U5") (pin "19") (pinfunction "IO5_19") (pintype "bidirectional"))
    )
    (net (code "4") (name "/CHG_FULL") (class "Default")
      (node (ref "R21") (pin "2") (pinfunction "2_2") (pintype "passive"))
      (node (ref "U6") (pin "4") (pinfunction "Y_4") (pintype "output"))
    )
    (net (code "5") (name "/DTR") (class "Default")
      (node (ref "Q5") (pin "2") (pinfunction "E_2") (pintype "passive"))
      (node (ref "R26") (pin "1") (pinfunction "1_1") (pintype "passive"))
      (node (ref "U7") (pin "28") (pinfunction "DTR_28") (pintype "passive"))
    )
    (net (code "6") (name "/EN") (class "Default")
      (node (ref "C19") (pin "1") (pinfunction "1_1") (pintype "passive"))
      (node (ref "D4") (pin "4") (pinfunction "C4_4") (pintype "passive"))
      (node (ref "Q4") (pin "3") (pinfunction "C_3") (pintype "passive"))
      (node (ref "R11") (pin "2") (pinfunction "2_2") (pintype "passive"))
      (node (ref "S4") (pin "3") (pinfunction "3_3") (pintype "passive"))
      (node (ref "U5") (pin "8") (pinfunction "EN_8") (pintype "input"))
    )
    (net (code "7") (name "/GPIO8{slash}SCL") (class "Default")
      (node (ref "R15") (pin "1") (pinfunction "1_1") (pintype "passive"))
      (node (ref "TP10") (pin "1") (pinfunction "TPoint_1") (pintype "passive"))
      (node (ref "U5") (pin "22") (pinfunction "IO8_22") (pintype "bidirectional"))
      (node (ref "U8") (pin "14") (pinfunction "SCL/SCLK_14") (pintype "passive"))
    )
    (net (code "8") (name "/GPIO9{slash}SDA") (class "Default")
      (node (ref "Q5") (pin "3") (pinfunction "C_3") (pintype "passive"))
      (node (ref "R16") (pin "1") (pinfunction "1_1") (pintype "passive"))
      (node (ref "TP11") (pin "1") (pinfunction "TPoint_1") (pintype "passive"))
      (node (ref "U5") (pin "23") (pinfunction "IO9_23") (pintype "bidirectional"))
      (node (ref "U8") (pin "13") (pinfunction "SDA/SDI/SDIO_13") (pintype "passive"))
    )
    (net (code "9") (name "/MODEM") (class "Default")
      (node (ref "TP7") (pin "1") (pinfunction "TPoint_1") (pintype "passive"))
      (node (ref "U1") (pin "42") (pinfunction "GPIO1_42") (pintype "bidirectional"))
      (node (ref "U5") (pin "16") (pinfunction "IO10_16") (pintype "bidirectional"))
    )
    (net (code "10") (name "/MODEM_RX") (class "Default")
      (node (ref "D3") (pin "2") (pinfunction "C2_2") (pintype "passive"))
      (node (ref "R1") (pin "2") (pinfunction "2_2") (pintype "passive"))
      (node (ref "TP6") (pin "1") (pinfunction "TPoint_1") (pintype "passive"))
      (node (ref "U5") (pin "27") (pinfunction "IO19_27") (pintype "bidirectional"))
    )
    (net (code "11") (name "/MODEM_TX") (class "Default")
      (node (ref "D3") (pin "1") (pinfunction "C1_1") (pintype "passive"))
      (node (ref "R32") (pin "2") (pinfunction "2_2") (pintype "passive"))
      (node (ref "TP5") (pin "1") (pinfunction "TPoint_1") (pintype "passive"))
      (node (ref "U5") (pin "26") (pinfunction "IO18_26") (pintype "bidirectional"))
    )
    (net (code "12") (name "/PAIRING") (class "Default")
      (node (ref "C12") (pin "2") (pinfunction "2_2") (pintype "passive"))
      (node (ref "D4") (pin "1") (pinfunction "C1_1") (pintype "passive"))
      (node (ref "R5") (pin "1") (pinfunction "1_1") (pintype "passive"))
      (node (ref "S2") (pin "3") (pinfunction "3_3") (pintype "passive"))
      (node (ref "U5") (pin "21") (pinfunction "IO7_21") (pintype "bidirectional"))
    )
    (net (code "13") (name "/P_EN") (class "Default")
      (node (ref "R3") (pin "2") (pinfunction "2_2") (pintype "passive"))
      (node (ref "U2") (pin "3") (pinfunction "EN_3") (pintype "passive"))
    )
    (net (code "14") (name "/RTS") (class "Default")
      (node (ref "Q4") (pin "2") (pinfunction "E_2") (pintype "passive"))
      (node (ref "R27") (pin "1") (pinfunction "1_1") (pintype "passive"))
      (node (ref "U7") (pin "23") (pinfunction "CTS_23") (pintype "passive"))
    )
    (net (code "15") (name "/RXD0") (class "Default")
      (node (ref "R19") (pin "2") (pinfunction "2_2") (pintype "passive"))
      (node (ref "U5") (pin "30") (pinfunction "RXD0_30") (pintype "bidirectional"))
    )
    (net (code "16") (name "/STAT") (class "Default")
      (node (ref "R14") (pin "2") (pinfunction "2_2") (pintype "passive"))
      (node (ref "R29") (pin "1") (pinfunction "1_1") (pintype "passive"))
      (node (ref "U4") (pin "1") (pinfunction "STAT_1") (pintype "passive"))
      (node (ref "U6") (pin "2") (pinfunction "A_2") (pintype "input"))
    )
    (net (code "17") (name "/STATUS") (class "Default")
      (node (ref "R13") (pin "2") (pinfunction "2_2") (pintype "passive"))
      (node (ref "U5") (pin "5") (pinfunction "IO2_5") (pintype "bidirectional"))
    )
    (net (code "18") (name "/SW") (class "Default")
      (node (ref "L1") (pin "1") (pinfunction "1_1") (pintype "passive"))
      (node (ref "U2") (pin "5") (pinfunction "LX_5") (pintype "passive"))
    )
    (net (code "19") (name "/TXD0") (class "Default")
      (node (ref "R20") (pin "2") (pinfunction "2_2") (pintype "passive"))
      (node (ref "U5") (pin "31") (pinfunction "TXD0_31") (pintype "bidirectional"))
    )
    (net (code "20") (name "/U0RX_CP") (class "Default")
      (node (ref "R19") (pin "1") (pinfunction "1_1") (pintype "passive"))
      (node (ref "TP8") (pin "1") (pinfunction "TPoint_1") (pintype "passive"))
      (node (ref "U7") (pin "26") (pinfunction "TXD_26") (pintype "passive"))
    )
    (net (code "21") (name "/U0TX_CP") (class "Default")
      (node (ref "R20") (pin "1") (pinfunction "1_1") (pintype "passive"))
      (node (ref "TP9") (pin "1") (pinfunction "TPoint_1") (pintype "passive"))
      (node (ref "U7") (pin "25") (pinfunction "RXD_25") (pintype "passive"))
    )
    (net (code "22") (name "/USBC_N") (class "Default")
      (node (ref "D6") (pin "6") (pinfunction "D1c_6") (pintype "passive"))
      (node (ref "J1") (pin "A7") (pinfunction "D1-_A7") (pintype "bidirectional"))
      (node (ref "J1") (pin "B7") (pinfunction "D2-_B7") (pintype "bidirectional"))
    )
    (net (code "23") (name "/USBC_P") (class "Default")
      (node (ref "D6") (pin "4") (pinfunction "D2c_4") (pintype "passive"))
      (node (ref "J1") (pin "A6") (pinfunction "D1+_A6") (pintype "bidirectional"))
      (node (ref "J1") (pin "B6") (pinfunction "D2+_B6") (pintype "bidirectional"))
    )
    (net (code "24") (name "/USB_N") (class "Default")
      (node (ref "D6") (pin "1") (pinfunction "D1i_1") (pintype "passive"))
      (node (ref "U7") (pin "5") (pinfunction "D-_5") (pintype "passive"))
    )
    (net (code "25") (name "/USB_P") (class "Default")
      (node (ref "D6") (pin "3") (pinfunction "D2i_3") (pintype "passive"))
      (node (ref "U7") (pin "4") (pinfunction "D+_4") (pintype "passive"))
    )
    (net (code "26") (name "/VIN") (class "Default")
      (node (ref "C4") (pin "2") (pinfunction "2_2") (pintype "passive"))
      (node (ref "C6") (pin "2") (pinfunction "2_2") (pintype "passive"))
      (node (ref "D1") (pin "1") (pinfunction "K_1") (pintype "passive"))
      (node (ref "Q1") (pin "3") (pinfunction "3_3") (pintype "passive"))
      (node (ref "R3") (pin "1") (pinfunction "1_1") (pintype "passive"))
      (node (ref "TP2") (pin "1") (pinfunction "TPoint_1") (pintype "passive"))
      (node (ref "U2") (pin "4") (pinfunction "VIN_4") (pintype "passive"))
    )
    (net (code "27") (name "/WAKEUP") (class "Default")
      (node (ref "C13") (pin "2") (pinfunction "2_2") (pintype "passive"))
      (node (ref "D4") (pin "3") (pinfunction "C3_3") (pintype "passive"))
      (node (ref "R6") (pin "1") (pinfunction "1_1") (pintype "passive"))
      (node (ref "S3") (pin "3") (pinfunction "3_3") (pintype "passive"))
      (node (ref "U5") (pin "20") (pinfunction "IO6_20") (pintype "bidirectional"))
    )
    (net (code "28") (name "GND") (class "Default")
      (node (ref "C1") (pin "2") (pinfunction "2_2") (pintype "passive"))
      (node (ref "C10") (pin "2") (pinfunction "2_2") (pintype "passive"))
      (node (ref "C11") (pin "1") (pinfunction "1_1") (pintype "passive"))
      (node (ref "C12") (pin "1") (pinfunction "1_1") (pintype "passive"))
      (node (ref "C13") (pin "1") (pinfunction "1_1") (pintype "passive"))
      (node (ref "C14") (pin "1") (pinfunction "1_1") (pintype "passive"))
      (node (ref "C15") (pin "1") (pinfunction "1_1") (pintype "passive"))
      (node (ref "C16") (pin "1") (pinfunction "1_1") (pintype "passive"))
      (node (ref "C17") (pin "1") (pinfunction "1_1") (pintype "passive"))
      (node (ref "C18") (pin "2") (pinfunction "2_2") (pintype "passive"))
      (node (ref "C19") (pin "2") (pinfunction "2_2") (pintype "passive"))
      (node (ref "C2") (pin "1") (pinfunction "1_1") (pintype "passive"))
      (node (ref "C20") (pin "2") (pinfunction "2_2") (pintype "passive"))
      (node (ref "C21") (pin "2") (pinfunction "2_2") (pintype "passive"))
      (node (ref "C22") (pin "2") (pinfunction "2_2") (pintype "passive"))
      (node (ref "C23") (pin "2") (pinfunction "2_2") (pintype "passive"))
      (node (ref "C24") (pin "1") (pinfunction "1_1") (pintype "passive"))
      (node (ref "C25") (pin "1") (pinfunction "1_1") (pintype "passive"))
      (node (ref "C26") (pin "1") (pinfunction "1_1") (pintype "passive"))
      (node (ref "C27") (pin "1") (pinfunction "1_1") (pintype "passive"))
      (node (ref "C28") (pin "1") (pinfunction "1_1") (pintype "passive"))
      (node (ref "C29") (pin "1") (pinfunction "1_1") (pintype "passive"))
      (node (ref "C3") (pin "1") (pinfunction "1_1") (pintype "passive"))
      (node (ref "C30") (pin "1") (pinfunction "1_1") (pintype "passive"))
      (node (ref "C31") (pin "1") (pinfunction "1_1") (pintype "passive"))
      (node (ref "C4") (pin "1") (pinfunction "1_1") (pintype "passive"))
      (node (ref "C5") (pin "1") (pinfunction "1_1") (pintype "passive"))
      (node (ref "C6") (pin "1") (pinfunction "1_1") (pintype "passive"))
      (node (ref "C7") (pin "1") (pinfunction "1_1") (pintype "passive"))
      (node (ref "C8") (pin "2") (pinfunction "2_2") (pintype "passive"))
      (node (ref "C9") (pin "1") (pinfunction "1_1") (pintype "passive"))
      (node (ref "D2") (pin "2") (pinfunction "A_2") (pintype "passive"))
      (node (ref "D3") (pin "7") (pinfunction "Anode_7") (pintype "passive"))
      (node (ref "D4") (pin "7") (pinfunction "Anode_7") (pintype "passive"))
      (node (ref "D5") (pin "2") (pinfunction "A_2") (pintype "passive"))
      (node (ref "D6") (pin "2") (pinfunction "GND_2") (pintype "passive"))
      (node (ref "FL1") (pin "2") (pinfunction "2_2") (pintype "passive"))
      (node (ref "J1") (pin "A1") (pinfunction "GND_A_A1") (pintype "power_in"))
      (node (ref "J1") (pin "A12") (pinfunction "GND_A_A12") (pintype "power_in"))
      (node (ref "J1") (pin "B1") (pinfunction "GND_B_B1") (pintype "power_in"))
      (node (ref "J1") (pin "B12") (pinfunction "GND_B_B12") (pintype "power_in"))
      (node (ref "J1") (pin "G1") (pinfunction "GND/SHIELD_G1") (pintype "power_in"))
      (node (ref "J1") (pin "G2") (pinfunction "GND/SHIELD_G2") (pintype "power_in"))
      (node (ref "J1") (pin "S1") (pinfunction "GND/SHIELD_S1") (pintype "power_in"))
      (node (ref "J1") (pin "S2") (pinfunction "GND/SHIELD_S2") (pintype "power_in"))
      (node (ref "J1") (pin "S3") (pinfunction "GND/SHIELD_S3") (pintype "power_in"))
      (node (ref "J1") (pin "S4") (pinfunction "GND/SHIELD_S4") (pintype "power_in"))
      (node (ref "LED2") (pin "C") (pinfunction "C_C") (pintype "passive"))
      (node (ref "LED3") (pin "C") (pinfunction "C_C") (pintype "passive"))
      (node (ref "LED4") (pin "C") (pinfunction "C_C") (pintype "passive"))
      (node (ref "Q3") (pin "2") (pinfunction "2_2") (pintype "passive"))
      (node (ref "R10") (pin "2") (pinfunction "2_2") (pintype "passive"))
      (node (ref "R12") (pin "2") (pinfunction "2_2") (pintype "passive"))
      (node (ref "R2") (pin "2") (pinfunction "2_2") (pintype "passive"))
      (node (ref "R24") (pin "2") (pinfunction "2_2") (pintype "passive"))
      (node (ref "R25") (pin "2") (pinfunction "2_2") (pintype "passive"))
      (node (ref "R33") (pin "2") (pinfunction "2_2") (pintype "passive"))
      (node (ref "R35") (pin "2") (pinfunction "2_2") (pintype "passive"))
      (node (ref "R5") (pin "2") (pinfunction "2_2") (pintype "passive"))
      (node (ref "R6") (pin "2") (pinfunction "2_2") (pintype "passive"))
      (node (ref "R9") (pin "2") (pinfunction "2_2") (pintype "passive"))
      (node (ref "S1") (pin "M") (pinfunction "M_M") (pintype "passive"))
      (node (ref "S2") (pin "M") (pinfunction "M_M") (pintype "passive"))
      (node (ref "S3") (pin "M") (pinfunction "M_M") (pintype "passive"))
      (node (ref "S4") (pin "1") (pinfunction "1_1") (pintype "passive"))
      (node (ref "S4") (pin "M") (pinfunction "M_M") (pintype "passive"))
      (node (ref "T1") (pin "2") (pinfunction "GND_2") (pintype "passive"))
      (node (ref "U1") (pin "15") (pinfunction "GND_15_15") (pintype "power_in"))
      (node (ref "U1") (pin "18") (pinfunction "GND_18_18") (pintype "power_in"))
      (node (ref "U1") (pin "21") (pinfunction "GND_21_21") (pintype "power_in"))
      (node (ref "U1") (pin "26") (pinfunction "GND_26_26") (pintype "power_in"))
      (node (ref "U1") (pin "27") (pinfunction "GND_27_27") (pintype "power_in"))
      (node (ref "U1") (pin "29") (pinfunction "GND_29_29") (pintype "power_in"))
      (node (ref "U1") (pin "34") (pinfunction "GND_34_34") (pintype "power_in"))
      (node (ref "U1") (pin "35") (pinfunction "GND_35_35") (pintype "power_in"))
      (node (ref "U1") (pin "37") (pinfunction "GND_37_37") (pintype "power_in"))
      (node (ref "U1") (pin "4") (pinfunction "GND_4_4") (pintype "power_in"))
      (node (ref "U1") (pin "40") (pinfunction "GND_40_40") (pintype "power_in"))
      (node (ref "U1") (pin "43") (pinfunction "GND_43_43") (pintype "power_in"))
      (node (ref "U1") (pin "50") (pinfunction "GND_50_50") (pintype "power_in"))
      (node (ref "U1") (pin "53") (pinfunction "SHIELD_53") (pintype "passive"))
      (node (ref "U1") (pin "54") (pinfunction "SHIELD_54") (pintype "passive"))
      (node (ref "U1") (pin "9") (pinfunction "GND_9_9") (pintype "power_in"))
      (node (ref "U1") (pin "S1_1") (pinfunction "SHIELD_S1_1") (pintype "passive"))
      (node (ref "U1") (pin "S1_2") (pinfunction "SHIELD_S1_2") (pintype "passive"))
      (node (ref "U1") (pin "S1_3") (pinfunction "SHIELD_S1_3") (pintype "passive"))
      (node (ref "U1") (pin "S2_1") (pinfunction "SHIELD_S2_1") (pintype "passive"))
      (node (ref "U1") (pin "S2_2") (pinfunction "SHIELD_S2_2") (pintype "passive"))
      (node (ref "U1") (pin "S2_3") (pinfunction "SHIELD_S2_3") (pintype "passive"))
      (node (ref "U2") (pin "9") (pinfunction "EP_9") (pintype "passive"))
      (node (ref "U4") (pin "2") (pinfunction "VSS_2") (pintype "passive"))
      (node (ref "U5") (pin "1") (pinfunction "GND_1") (pintype "power_in"))
      (node (ref "U5") (pin "11") (pinfunction "GND_11") (pintype "power_in"))
      (node (ref "U5") (pin "14") (pinfunction "GND_14") (pintype "power_in"))
      (node (ref "U5") (pin "2") (pinfunction "GND_2") (pintype "power_in"))
      (node (ref "U5") (pin "36") (pinfunction "GND_36") (pintype "power_in"))
      (node (ref "U5") (pin "37") (pinfunction "GND_37") (pintype "power_in"))
      (node (ref "U5") (pin "38") (pinfunction "GND_38") (pintype "power_in"))
      (node (ref "U5") (pin "39") (pinfunction "GND_39") (pintype "power_in"))
      (node (ref "U5") (pin "40") (pinfunction "GND_40") (pintype "power_in"))
      (node (ref "U5") (pin "41") (pinfunction "GND_41") (pintype "power_in"))
      (node (ref "U5") (pin "42") (pinfunction "GND_42") (pintype "power_in"))
      (node (ref "U5") (pin "43") (pinfunction "GND_43") (pintype "power_in"))
      (node (ref "U5") (pin "44") (pinfunction "GND_44") (pintype "power_in"))
      (node (ref "U5") (pin "45") (pinfunction "GND_45") (pintype "power_in"))
      (node (ref "U5") (pin "46") (pinfunction "GND_46") (pintype "power_in"))
      (node (ref "U5") (pin "47") (pinfunction "GND_47") (pintype "power_in"))
      (node (ref "U5") (pin "48") (pinfunction "GND_48") (pintype "power_in"))
      (node (ref "U5") (pin "49_1") (pinfunction "GND_49_1") (pintype "power_in"))
      (node (ref "U5") (pin "49_2") (pinfunction "GND_49_2") (pintype "power_in"))
      (node (ref "U5") (pin "49_3") (pinfunction "GND_49_3") (pintype "power_in"))
      (node (ref "U5") (pin "49_4") (pinfunction "GND_49_4") (pintype "power_in"))
      (node (ref "U5") (pin "49_5") (pinfunction "GND_49_5") (pintype "power_in"))
      (node (ref "U5") (pin "49_6") (pinfunction "GND_49_6") (pintype "power_in"))
      (node (ref "U5") (pin "49_7") (pinfunction "GND_49_7") (pintype "power_in"))
      (node (ref "U5") (pin "49_8") (pinfunction "GND_49_8") (pintype "power_in"))
      (node (ref "U5") (pin "49_9") (pinfunction "GND_49_9") (pintype "power_in"))
      (node (ref "U5") (pin "50") (pinfunction "GND_50") (pintype "power_in"))
      (node (ref "U5") (pin "51") (pinfunction "GND_51") (pintype "power_in"))
      (node (ref "U5") (pin "52") (pinfunction "GND_52") (pintype "power_in"))
      (node (ref "U5") (pin "53") (pinfunction "GND_53") (pintype "power_in"))
      (node (ref "U6") (pin "3") (pinfunction "GND_3") (pintype "power_in"))
      (node (ref "U7") (pin "29") (pinfunction "PAD_29") (pintype "passive"))
      (node (ref "U7") (pin "3") (pinfunction "GND_3") (pintype "passive"))
      (node (ref "U8") (pin "2") (pinfunction "GND_1_2") (pintype "passive"))
      (node (ref "U8") (pin "4") (pinfunction "GND_2_4") (pintype "passive"))
      (node (ref "U8") (pin "5") (pinfunction "GND_3_5") (pintype "passive"))
    )
    (net (code "29") (name "Net-(C31-Pad2)") (class "Default")
      (node (ref "C31") (pin "2") (pinfunction "2_2") (pintype "passive"))
      (node (ref "R34") (pin "2") (pinfunction "2_2") (pintype "passive"))
    )
    (net (code "30") (name "Net-(LED1-PadC)") (class "Default")
      (node (ref "LED1") (pin "C") (pinfunction "C_C") (pintype "passive"))
      (node (ref "R14") (pin "1") (pinfunction "1_1") (pintype "passive"))
    )
    (net (code "31") (name "Net-(LED2-PadA)") (class "Default")
      (node (ref "LED2") (pin "A") (pinfunction "A_A") (pintype "passive"))
      (node (ref "R13") (pin "1") (pinfunction "1_1") (pintype "passive"))
    )
    (net (code "32") (name "Net-(LED3-PadA)") (class "Default")
      (node (ref "LED3") (pin "A") (pinfunction "A_A") (pintype "passive"))
      (node (ref "R17") (pin "1") (pinfunction "1_1") (pintype "passive"))
    )
    (net (code "33") (name "Net-(LED4-PadA)") (class "Default")
      (node (ref "LED4") (pin "A") (pinfunction "A_A") (pintype "passive"))
      (node (ref "R21") (pin "1") (pinfunction "1_1") (pintype "passive"))
    )
    (net (code "34") (name "Net-(Q2-Pad1)") (class "Default")
      (node (ref "Q2") (pin "1") (pinfunction "1_1") (pintype "passive"))
      (node (ref "Q3") (pin "3") (pinfunction "3_3") (pintype "passive"))
      (node (ref "R4") (pin "2") (pinfunction "2_2") (pintype "passive"))
    )
    (net (code "35") (name "Net-(Q2-Pad3)") (class "Default")
      (node (ref "Q2") (pin "3") (pinfunction "3_3") (pintype "passive"))
      (node (ref "R7") (pin "1") (pinfunction "1_1") (pintype "passive"))
    )
    (net (code "36") (name "Net-(Q3-Pad1)") (class "Default")
      (node (ref "Q3") (pin "1") (pinfunction "1_1") (pintype "passive"))
      (node (ref "R10") (pin "1") (pinfunction "1_1") (pintype "passive"))
      (node (ref "R8") (pin "2") (pinfunction "2_2") (pintype "passive"))
    )
    (net (code "37") (name "Net-(Q4-B)") (class "Default")
      (node (ref "Q4") (pin "1") (pinfunction "B_1") (pintype "passive"))
      (node (ref "R26") (pin "2") (pinfunction "2_2") (pintype "passive"))
    )
    (net (code "38") (name "Net-(Q5-B)") (class "Default")
      (node (ref "Q5") (pin "1") (pinfunction "B_1") (pintype "passive"))
      (node (ref "R27") (pin "2") (pinfunction "2_2") (pintype "passive"))
    )
    (net (code "39") (name "Net-(U1-UART_RX)") (class "Default")
      (node (ref "R1") (pin "1") (pinfunction "1_1") (pintype "passive"))
      (node (ref "U1") (pin "11") (pinfunction "UART_RX_11") (pintype "bidirectional"))
    )
    (net (code "40") (name "Net-(U1-UART_TX)") (class "Default")
      (node (ref "R32") (pin "1") (pinfunction "1_1") (pintype "passive"))
      (node (ref "U1") (pin "13") (pinfunction "UART_TX_13") (pintype "bidirectional"))
    )
    (net (code "41") (name "Net-(U2-COMP)") (class "Default")
      (node (ref "R34") (pin "1") (pinfunction "1_1") (pintype "passive"))
      (node (ref "U2") (pin "1") (pinfunction "COMP_1") (pintype "passive"))
    )
    (net (code "42") (name "Net-(U2-FB)") (class "Default")
      (node (ref "R31") (pin "2") (pinfunction "2_2") (pintype "passive"))
      (node (ref "R33") (pin "1") (pinfunction "1_1") (pintype "passive"))
      (node (ref "U2") (pin "7") (pinfunction "FB_7") (pintype "passive"))
    )
    (net (code "43") (name "Net-(U2-RT)") (class "Default")
      (node (ref "R35") (pin "1") (pinfunction "1_1") (pintype "passive"))
      (node (ref "U2") (pin "6") (pinfunction "RT_6") (pintype "passive"))
    )
    (net (code "44") (name "Net-(U2-SS)") (class "Default")
      (node (ref "C30") (pin "2") (pinfunction "2_2") (pintype "passive"))
      (node (ref "U2") (pin "2") (pinfunction "SS_2") (pintype "passive"))
    )
    (net (code "45") (name "Net-(U4-PROG)") (class "Default")
      (node (ref "R12") (pin "1") (pinfunction "1_1") (pintype "passive"))
      (node (ref "U4") (pin "5") (pinfunction "PROG_5") (pintype "passive"))
    )
    (net (code "46") (name "Net-(U5-IO0)") (class "Default")
      (node (ref "C21") (pin "1") (pinfunction "1_1") (pintype "passive"))
      (node (ref "R18") (pin "1") (pinfunction "1_1") (pintype "passive"))
      (node (ref "U5") (pin "12") (pinfunction "IO0_12") (pintype "bidirectional"))
      (node (ref "Y1") (pin "2") (pinfunction "2_2") (pintype "passive"))
    )
    (net (code "47") (name "Net-(U5-IO1)") (class "Default")
      (node (ref "C22") (pin "1") (pinfunction "1_1") (pintype "passive"))
      (node (ref "R18") (pin "2") (pinfunction "2_2") (pintype "passive"))
      (node (ref "U5") (pin "13") (pinfunction "IO1_13") (pintype "bidirectional"))
      (node (ref "Y1") (pin "1") (pinfunction "1_1") (pintype "passive"))
    )
    (net (code "48") (name "Net-(U5-IO3)") (class "Default")
      (node (ref "R29") (pin "2") (pinfunction "2_2") (pintype "passive"))
      (node (ref "U5") (pin "6") (pinfunction "IO3_6") (pintype "bidirectional"))
    )
    (net (code "49") (name "Net-(U7-VBUS)") (class "Default")
      (node (ref "R22") (pin "2") (pinfunction "2_2") (pintype "passive"))
      (node (ref "R24") (pin "1") (pinfunction "1_1") (pintype "passive"))
      (node (ref "U7") (pin "8") (pinfunction "VBUS_8") (pintype "passive"))
    )
    (net (code "50") (name "Net-(U7-~{RST})") (class "Default")
      (node (ref "R23") (pin "2") (pinfunction "2_2") (pintype "passive"))
      (node (ref "U7") (pin "9") (pinfunction "~{RST}_9") (pintype "passive"))
    )
    (net (code "51") (name "Net-(U8-SDO{slash}ALT_ADDRESS)") (class "Default")
      (node (ref "R25") (pin "1") (pinfunction "1_1") (pintype "passive"))
      (node (ref "U8") (pin "12") (pinfunction "SDO/ALT_ADDRESS_12") (pintype "passive"))
    )
    (net (code "52") (name "Net-(U8-~{CS})") (class "Default")
      (node (ref "R28") (pin "1") (pinfunction "1_1") (pintype "passive"))
      (node (ref "U8") (pin "7") (pinfunction "~{CS}_7") (pintype "passive"))
    )
    (net (code "53") (name "VBAT") (class "Default")
      (node (ref "C23") (pin "1") (pinfunction "1_1") (pintype "passive"))
      (node (ref "Q1") (pin "2") (pinfunction "2_2") (pintype "passive"))
      (node (ref "Q2") (pin "2") (pinfunction "2_2") (pintype "passive"))
      (node (ref "R4") (pin "1") (pinfunction "1_1") (pintype "passive"))
      (node (ref "S1") (pin "3") (pinfunction "3_3") (pintype "passive"))
      (node (ref "TP1") (pin "1") (pinfunction "TPoint_1") (pintype "passive"))
      (node (ref "U6") (pin "5") (pinfunction "VCC_5") (pintype "power_in"))
    )
    (net (code "54") (name "VBAT_IN") (class "Default")
      (node (ref "C15") (pin "2") (pinfunction "2_2") (pintype "passive"))
      (node (ref "D5") (pin "1") (pinfunction "K_1") (pintype "passive"))
      (node (ref "S1") (pin "2") (pinfunction "2_2") (pintype "passive"))
      (node (ref "T1") (pin "1") (pinfunction "VBAT_1") (pintype "passive"))
      (node (ref "U4") (pin "3") (pinfunction "VBAT_3") (pintype "passive"))
    )
    (net (code "55") (name "VBUS_USB") (class "Default")
      (node (ref "C16") (pin "2") (pinfunction "2_2") (pintype "passive"))
      (node (ref "C26") (pin "2") (pinfunction "2_2") (pintype "passive"))
      (node (ref "C27") (pin "2") (pinfunction "2_2") (pintype "passive"))
      (node (ref "C29") (pin "2") (pinfunction "2_2") (pintype "passive"))
      (node (ref "D1") (pin "2") (pinfunction "A_2") (pintype "passive"))
      (node (ref "D2") (pin "1") (pinfunction "K_1") (pintype "passive"))
      (node (ref "J1") (pin "A4") (pinfunction "VBUS_A_A4") (pintype "power_in"))
      (node (ref "J1") (pin "A9") (pinfunction "VBUS_A_A9") (pintype "power_in"))
      (node (ref "J1") (pin "B4") (pinfunction "VBUS_B_B4") (pintype "power_in"))
      (node (ref "J1") (pin "B9") (pinfunction "VBUS_B_B9") (pintype "power_in"))
      (node (ref "LED1") (pin "A") (pinfunction "A_A") (pintype "passive"))
      (node (ref "Q1") (pin "1") (pinfunction "1_1") (pintype "passive"))
      (node (ref "R2") (pin "1") (pinfunction "1_1") (pintype "passive"))
      (node (ref "R22") (pin "1") (pinfunction "1_1") (pintype "passive"))
      (node (ref "U4") (pin "4") (pinfunction "VDD_4") (pintype "passive"))
      (node (ref "U7") (pin "7") (pinfunction "VREGIN_7") (pintype "passive"))
    )
    (net (code "56") (name "VIO_CP") (class "Default")
      (node (ref "C25") (pin "2") (pinfunction "2_2") (pintype "passive"))
      (node (ref "C28") (pin "2") (pinfunction "2_2") (pintype "passive"))
      (node (ref "R23") (pin "1") (pinfunction "1_1") (pintype "passive"))
      (node (ref "U7") (pin "6") (pinfunction "VDD_6") (pintype "passive"))
    )
    (net (code "57") (name "Vmodem") (class "Default")
      (node (ref "C1") (pin "1") (pinfunction "1_1") (pintype "passive"))
      (node (ref "C10") (pin "1") (pinfunction "1_1") (pintype "passive"))
      (node (ref "C11") (pin "2") (pinfunction "2_2") (pintype "passive"))
      (node (ref "C14") (pin "2") (pinfunction "2_2") (pintype "passive"))
      (node (ref "C2") (pin "2") (pinfunction "2_2") (pintype "passive"))
      (node (ref "C3") (pin "2") (pinfunction "2_2") (pintype "passive"))
      (node (ref "C7") (pin "2") (pinfunction "2_2") (pintype "passive"))
      (node (ref "C8") (pin "1") (pinfunction "1_1") (pintype "passive"))
      (node (ref "C9") (pin "2") (pinfunction "2_2") (pintype "passive"))
      (node (ref "FL1") (pin "3") (pinfunction "OUT/IN_3") (pintype "passive"))
      (node (ref "U1") (pin "2") (pinfunction "VDD_2_2") (pintype "power_in"))
      (node (ref "U1") (pin "39") (pinfunction "VDD_39_39") (pintype "power_in"))
      (node (ref "U1") (pin "41") (pinfunction "VDD_41_41") (pintype "power_in"))
      (node (ref "U1") (pin "52") (pinfunction "VDD_52_52") (pintype "power_in"))
    )
    (net (code "58") (name "unconnected-(D3-C3-Pad3)") (class "Default")
      (node (ref "D3") (pin "3") (pinfunction "C3_3") (pintype "passive"))
    )
    (net (code "59") (name "unconnected-(D3-C4-Pad4)") (class "Default")
      (node (ref "D3") (pin "4") (pinfunction "C4_4") (pintype "passive"))
    )
    (net (code "60") (name "unconnected-(D3-C5-Pad5)") (class "Default")
      (node (ref "D3") (pin "5") (pinfunction "C5_5") (pintype "passive"))
    )
    (net (code "61") (name "unconnected-(D3-C6-Pad6)") (class "Default")
      (node (ref "D3") (pin "6") (pinfunction "C6_6") (pintype "passive"))
    )
    (net (code "62") (name "unconnected-(D4-C2-Pad2)") (class "Default")
      (node (ref "D4") (pin "2") (pinfunction "C2_2") (pintype "passive"))
    )
    (net (code "63") (name "unconnected-(D4-C5-Pad5)") (class "Default")
      (node (ref "D4") (pin "5") (pinfunction "C5_5") (pintype "passive"))
    )
    (net (code "64") (name "unconnected-(D4-C6-Pad6)") (class "Default")
      (node (ref "D4") (pin "6") (pinfunction "C6_6") (pintype "passive"))
    )
    (net (code "65") (name "unconnected-(D6-VBUS-Pad5)") (class "Default")
      (node (ref "D6") (pin "5") (pinfunction "VBUS_5") (pintype "passive"))
    )
    (net (code "66") (name "unconnected-(Fid1-Pad0)") (class "Default")
      (node (ref "Fid1") (pin "0") (pinfunction "0_0") (pintype "passive"))
    )
    (net (code "67") (name "unconnected-(Fid2-Pad0)") (class "Default")
      (node (ref "Fid2") (pin "0") (pinfunction "0_0") (pintype "passive"))
    )
    (net (code "68") (name "unconnected-(Fid3-Pad0)") (class "Default")
      (node (ref "Fid3") (pin "0") (pinfunction "0_0") (pintype "passive"))
    )
    (net (code "69") (name "unconnected-(J1-CC1-PadA5)") (class "Default")
      (node (ref "J1") (pin "A5") (pinfunction "CC1_A5") (pintype "bidirectional"))
    )
    (net (code "70") (name "unconnected-(J1-CC2-PadB5)") (class "Default")
      (node (ref "J1") (pin "B5") (pinfunction "CC2_B5") (pintype "bidirectional"))
    )
    (net (code "71") (name "unconnected-(J1-SBU1-PadA8)") (class "Default")
      (node (ref "J1") (pin "A8") (pinfunction "SBU1_A8") (pintype "bidirectional"))
    )
    (net (code "72") (name "unconnected-(J1-SBU2-PadB8)") (class "Default")
      (node (ref "J1") (pin "B8") (pinfunction "SBU2_B8") (pintype "bidirectional"))
    )
    (net (code "73") (name "unconnected-(S1-Pad1)") (class "Default")
      (node (ref "S1") (pin "1") (pinfunction "1_1") (pintype "passive"))
    )
    (net (code "74") (name "unconnected-(U1-NC_1-Pad1)") (class "Default")
      (node (ref "U1") (pin "1") (pinfunction "NC_1_1") (pintype "passive"))
    )
    (net (code "75") (name "unconnected-(U1-NC_3-Pad3)") (class "Default")
      (node (ref "U1") (pin "3") (pinfunction "NC_3_3") (pintype "passive"))
    )
    (net (code "76") (name "unconnected-(U1-NC_5-Pad5)") (class "Default")
      (node (ref "U1") (pin "5") (pinfunction "NC_5_5") (pintype "passive"))
    )
    (net (code "77") (name "unconnected-(U1-NC_6-Pad6)") (class "Default")
      (node (ref "U1") (pin "6") (pinfunction "NC_6_6") (pintype "passive"))
    )
    (net (code "78") (name "unconnected-(U1-NC_7-Pad7)") (class "Default")
      (node (ref "U1") (pin "7") (pinfunction "NC_7_7") (pintype "passive"))
    )
    (net (code "79") (name "unconnected-(U1-NC_8-Pad8)") (class "Default")
      (node (ref "U1") (pin "8") (pinfunction "NC_8_8") (pintype "passive"))
    )
    (net (code "80") (name "unconnected-(U1-NC_10-Pad10)") (class "Default")
      (node (ref "U1") (pin "10") (pinfunction "NC_10_10") (pintype "passive"))
    )
    (net (code "81") (name "unconnected-(U1-NC_12-Pad12)") (class "Default")
      (node (ref "U1") (pin "12") (pinfunction "NC_12_12") (pintype "passive"))
    )
    (net (code "82") (name "unconnected-(U1-NC_14-Pad14)") (class "Default")
      (node (ref "U1") (pin "14") (pinfunction "NC_14_14") (pintype "passive"))
    )
    (net (code "83") (name "unconnected-(U1-NC_16-Pad16)") (class "Default")
      (node (ref "U1") (pin "16") (pinfunction "NC_16_16") (pintype "passive"))
    )
    (net (code "84") (name "unconnected-(U1-NC_19-Pad19)") (class "Default")
      (node (ref "U1") (pin "19") (pinfunction "NC_19_19") (pintype "passive"))
    )
    (net (code "85") (name "unconnected-(U1-NC_20-Pad20)") (class "Default")
      (node (ref "U1") (pin "20") (pinfunction "NC_20_20") (pintype "passive"))
    )
    (net (code "86") (name "unconnected-(U1-NC_22-Pad22)") (class "Default")
      (node (ref "U1") (pin "22") (pinfunction "NC_22_22") (pintype "passive"))
    )
    (net (code "87") (name "unconnected-(U1-NC_23-Pad23)") (class "Default")
      (node (ref "U1") (pin "23") (pinfunction "NC_23_23") (pintype "passive"))
    )
    (net (code "88") (name "unconnected-(U1-NC_24-Pad24)") (class "Default")
      (node (ref "U1") (pin "24") (pinfunction "NC_24_24") (pintype "passive"))
    )
    (net (code "89") (name "unconnected-(U1-NC_25-Pad25)") (class "Default")
      (node (ref "U1") (pin "25") (pinfunction "NC_25_25") (pintype "passive"))
    )
    (net (code "90") (name "unconnected-(U1-NC_28-Pad28)") (class "Default")
      (node (ref "U1") (pin "28") (pinfunction "NC_28_28") (pintype "passive"))
    )
    (net (code "91") (name "unconnected-(U1-NC_30-Pad30)") (class "Default")
      (node (ref "U1") (pin "30") (pinfunction "NC_30_30") (pintype "passive"))
    )
    (net (code "92") (name "unconnected-(U1-NC_31-Pad31)") (class "Default")
      (node (ref "U1") (pin "31") (pinfunction "NC_31_31") (pintype "passive"))
    )
    (net (code "93") (name "unconnected-(U1-NC_32-Pad32)") (class "Default")
      (node (ref "U1") (pin "32") (pinfunction "NC_32_32") (pintype "passive"))
    )
    (net (code "94") (name "unconnected-(U1-NC_33-Pad33)") (class "Default")
      (node (ref "U1") (pin "33") (pinfunction "NC_33_33") (pintype "passive"))
    )
    (net (code "95") (name "unconnected-(U1-NC_36-Pad36)") (class "Default")
      (node (ref "U1") (pin "36") (pinfunction "NC_36_36") (pintype "passive"))
    )
    (net (code "96") (name "unconnected-(U1-NC_38-Pad38)") (class "Default")
      (node (ref "U1") (pin "38") (pinfunction "NC_38_38") (pintype "passive"))
    )
    (net (code "97") (name "unconnected-(U1-NC_44-Pad44)") (class "Default")
      (node (ref "U1") (pin "44") (pinfunction "NC_44_44") (pintype "passive"))
    )
    (net (code "98") (name "unconnected-(U1-NC_45-Pad45)") (class "Default")
      (node (ref "U1") (pin "45") (pinfunction "NC_45_45") (pintype "passive"))
    )
    (net (code "99") (name "unconnected-(U1-NC_46-Pad46)") (class "Default")
      (node (ref "U1") (pin "46") (pinfunction "NC_46_46") (pintype "passive"))
    )
    (net (code "100") (name "unconnected-(U1-NC_47-Pad47)") (class "Default")
      (node (ref "U1") (pin "47") (pinfunction "NC_47_47") (pintype "passive"))
    )
    (net (code "101") (name "unconnected-(U1-NC_48-Pad48)") (class "Default")
      (node (ref "U1") (pin "48") (pinfunction "NC_48_48") (pintype "passive"))
    )
    (net (code "102") (name "unconnected-(U1-NC_49-Pad49)") (class "Default")
      (node (ref "U1") (pin "49") (pinfunction "NC_49_49") (pintype "passive"))
    )
    (net (code "103") (name "unconnected-(U1-NC_51-Pad51)") (class "Default")
      (node (ref "U1") (pin "51") (pinfunction "NC_51_51") (pintype "passive"))
    )
    (net (code "104") (name "unconnected-(U1-T{slash}R_OUTPUT-Pad17)") (class "Default")
      (node (ref "U1") (pin "17") (pinfunction "T/R_OUTPUT_17") (pintype "passive"))
    )
    (net (code "105") (name "unconnected-(U2-PGOOD-Pad8)") (class "Default")
      (node (ref "U2") (pin "8") (pinfunction "PGOOD_8") (pintype "passive+no_connect"))
    )
    (net (code "106") (name "unconnected-(U5-NC-Pad4)") (class "Default")
      (node (ref "U5") (pin "4") (pinfunction "NC_4") (pintype "passive"))
    )
    (net (code "107") (name "unconnected-(U5-NC-Pad7)") (class "Default")
      (node (ref "U5") (pin "7") (pinfunction "NC_7") (pintype "passive"))
    )
    (net (code "108") (name "unconnected-(U5-NC-Pad9)") (class "Default")
      (node (ref "U5") (pin "9") (pinfunction "NC_9") (pintype "passive"))
    )
    (net (code "109") (name "unconnected-(U5-NC-Pad10)") (class "Default")
      (node (ref "U5") (pin "10") (pinfunction "NC_10") (pintype "passive"))
    )
    (net (code "110") (name "unconnected-(U5-NC-Pad15)") (class "Default")
      (node (ref "U5") (pin "15") (pinfunction "NC_15") (pintype "passive"))
    )
    (net (code "111") (name "unconnected-(U5-NC-Pad17)") (class "Default")
      (node (ref "U5") (pin "17") (pinfunction "NC_17") (pintype "passive"))
    )
    (net (code "112") (name "unconnected-(U5-NC-Pad24)") (class "Default")
      (node (ref "U5") (pin "24") (pinfunction "NC_24") (pintype "passive"))
    )
    (net (code "113") (name "unconnected-(U5-NC-Pad25)") (class "Default")
      (node (ref "U5") (pin "25") (pinfunction "NC_25") (pintype "passive"))
    )
    (net (code "114") (name "unconnected-(U5-NC-Pad28)") (class "Default")
      (node (ref "U5") (pin "28") (pinfunction "NC_28") (pintype "passive"))
    )
    (net (code "115") (name "unconnected-(U5-NC-Pad29)") (class "Default")
      (node (ref "U5") (pin "29") (pinfunction "NC_29") (pintype "passive"))
    )
    (net (code "116") (name "unconnected-(U5-NC-Pad32)") (class "Default")
      (node (ref "U5") (pin "32") (pinfunction "NC_32") (pintype "passive"))
    )
    (net (code "117") (name "unconnected-(U5-NC-Pad33)") (class "Default")
      (node (ref "U5") (pin "33") (pinfunction "NC_33") (pintype "passive"))
    )
    (net (code "118") (name "unconnected-(U5-NC-Pad34)") (class "Default")
      (node (ref "U5") (pin "34") (pinfunction "NC_34") (pintype "passive"))
    )
    (net (code "119") (name "unconnected-(U5-NC-Pad35)") (class "Default")
      (node (ref "U5") (pin "35") (pinfunction "NC_35") (pintype "passive"))
    )
    (net (code "120") (name "unconnected-(U6-NC-Pad1)") (class "Default")
      (node (ref "U6") (pin "1") (pinfunction "NC_1") (pintype "passive"))
    )
    (net (code "121") (name "unconnected-(U7-CHR0-Pad15)") (class "Default")
      (node (ref "U7") (pin "15") (pinfunction "CHR0_15") (pintype "passive"))
    )
    (net (code "122") (name "unconnected-(U7-CHR1-Pad14)") (class "Default")
      (node (ref "U7") (pin "14") (pinfunction "CHR1_14") (pintype "passive"))
    )
    (net (code "123") (name "unconnected-(U7-CHREN-Pad13)") (class "Default")
      (node (ref "U7") (pin "13") (pinfunction "CHREN_13") (pintype "passive"))
    )
    (net (code "124") (name "unconnected-(U7-DCD-Pad1)") (class "Default")
      (node (ref "U7") (pin "1") (pinfunction "DCD_1") (pintype "passive"))
    )
    (net (code "125") (name "unconnected-(U7-DSR-Pad27)") (class "Default")
      (node (ref "U7") (pin "27") (pinfunction "DSR_27") (pintype "passive"))
    )
    (net (code "126") (name "unconnected-(U7-GPIO.0{slash}TXT-Pad19)") (class "Default")
      (node (ref "U7") (pin "19") (pinfunction "GPIO.0/TXT_19") (pintype "passive"))
    )
    (net (code "127") (name "unconnected-(U7-GPIO.1{slash}RXT-Pad18)") (class "Default")
      (node (ref "U7") (pin "18") (pinfunction "GPIO.1/RXT_18") (pintype "passive"))
    )
    (net (code "128") (name "unconnected-(U7-GPIO.2{slash}RS485-Pad17)") (class "Default")
      (node (ref "U7") (pin "17") (pinfunction "GPIO.2/RS485_17") (pintype "passive"))
    )
    (net (code "129") (name "unconnected-(U7-GPIO.3{slash}WAKEUP-Pad16)") (class "Default")
      (node (ref "U7") (pin "16") (pinfunction "GPIO.3/WAKEUP_16") (pintype "passive"))
    )
    (net (code "130") (name "unconnected-(U7-GPIO.4-Pad22)") (class "Default")
      (node (ref "U7") (pin "22") (pinfunction "GPIO.4_22") (pintype "passive"))
    )
    (net (code "131") (name "unconnected-(U7-GPIO.5-Pad21)") (class "Default")
      (node (ref "U7") (pin "21") (pinfunction "GPIO.5_21") (pintype "passive"))
    )
    (net (code "132") (name "unconnected-(U7-GPIO.6-Pad20)") (class "Default")
      (node (ref "U7") (pin "20") (pinfunction "GPIO.6_20") (pintype "passive"))
    )
    (net (code "133") (name "unconnected-(U7-NC-Pad10)") (class "Default")
      (node (ref "U7") (pin "10") (pinfunction "NC_10") (pintype "passive"))
    )
    (net (code "134") (name "unconnected-(U7-RI{slash}CLK-Pad2)") (class "Default")
      (node (ref "U7") (pin "2") (pinfunction "RI/CLK_2") (pintype "passive"))
    )
    (net (code "135") (name "unconnected-(U7-RTS-Pad24)") (class "Default")
      (node (ref "U7") (pin "24") (pinfunction "RTS_24") (pintype "passive"))
    )
    (net (code "136") (name "unconnected-(U7-SUSPREND-Pad12)") (class "Default")
      (node (ref "U7") (pin "12") (pinfunction "SUSPREND_12") (pintype "passive"))
    )
    (net (code "137") (name "unconnected-(U7-~{SUSPREND}-Pad11)") (class "Default")
      (node (ref "U7") (pin "11") (pinfunction "~{SUSPREND}_11") (pintype "passive"))
    )
    (net (code "138") (name "unconnected-(U8-INT1-Pad8)") (class "Default")
      (node (ref "U8") (pin "8") (pinfunction "INT1_8") (pintype "passive"))
    )
    (net (code "139") (name "unconnected-(U8-INT2-Pad9)") (class "Default")
      (node (ref "U8") (pin "9") (pinfunction "INT2_9") (pintype "passive"))
    )
    (net (code "140") (name "unconnected-(U8-NC-Pad10)") (class "Default")
      (node (ref "U8") (pin "10") (pinfunction "NC_10") (pintype "passive"))
    )
    (net (code "141") (name "unconnected-(U8-RESERVED_1-Pad3)") (class "Default")
      (node (ref "U8") (pin "3") (pinfunction "RESERVED_1_3") (pintype "passive"))
    )
    (net (code "142") (name "unconnected-(U8-RESERVED_2-Pad11)") (class "Default")
      (node (ref "U8") (pin "11") (pinfunction "RESERVED_2_11") (pintype "passive"))
    )
  )
)
